# USBHubAndSensors.net
KiCad netlist of a schematic drawn in EAGLE
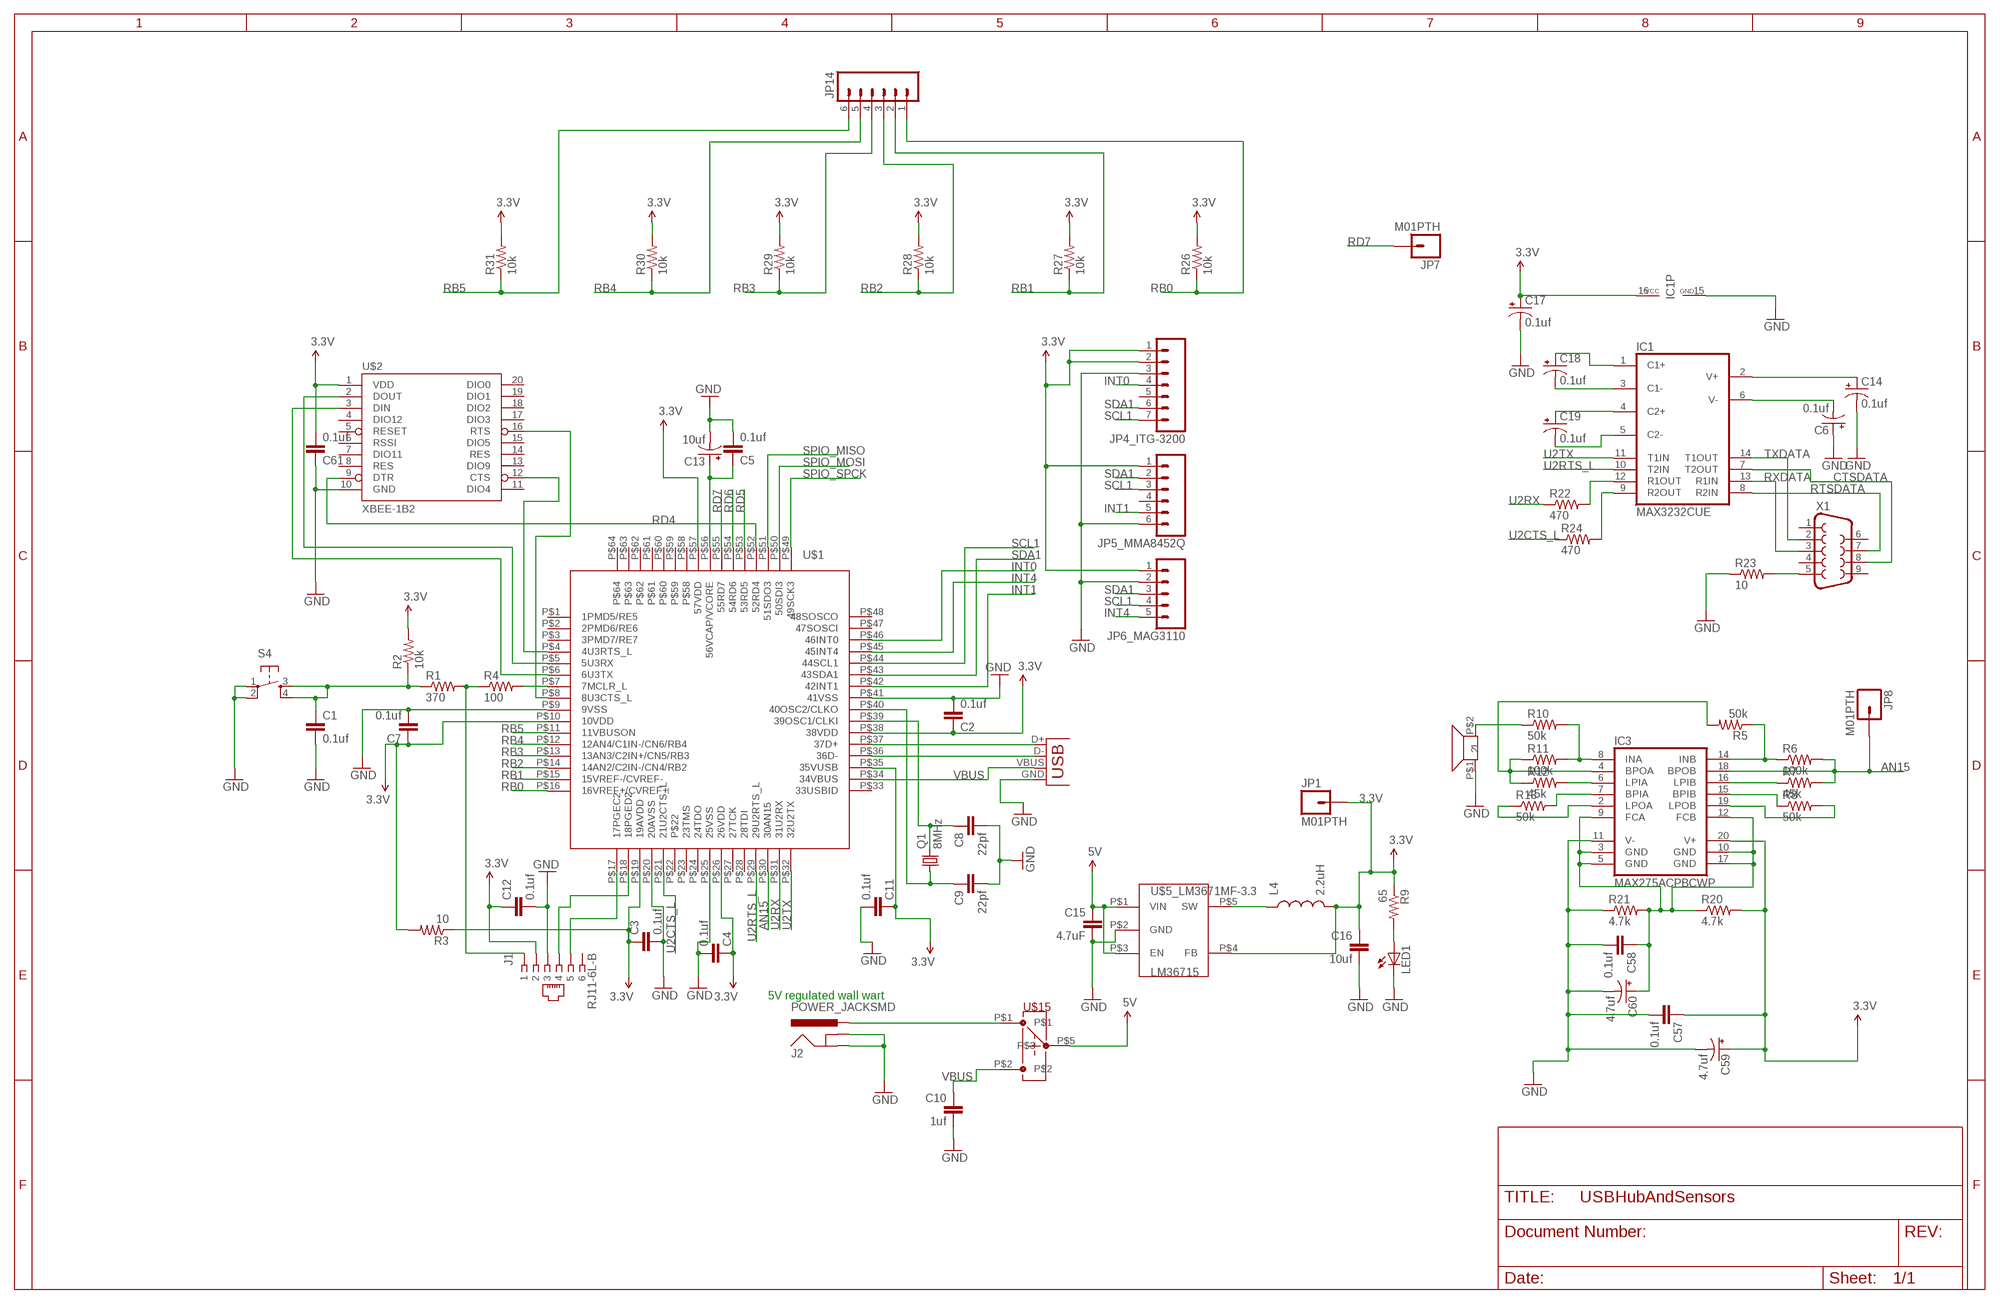
[diagram p0: schematic, sheet 1, part 1 of 2]
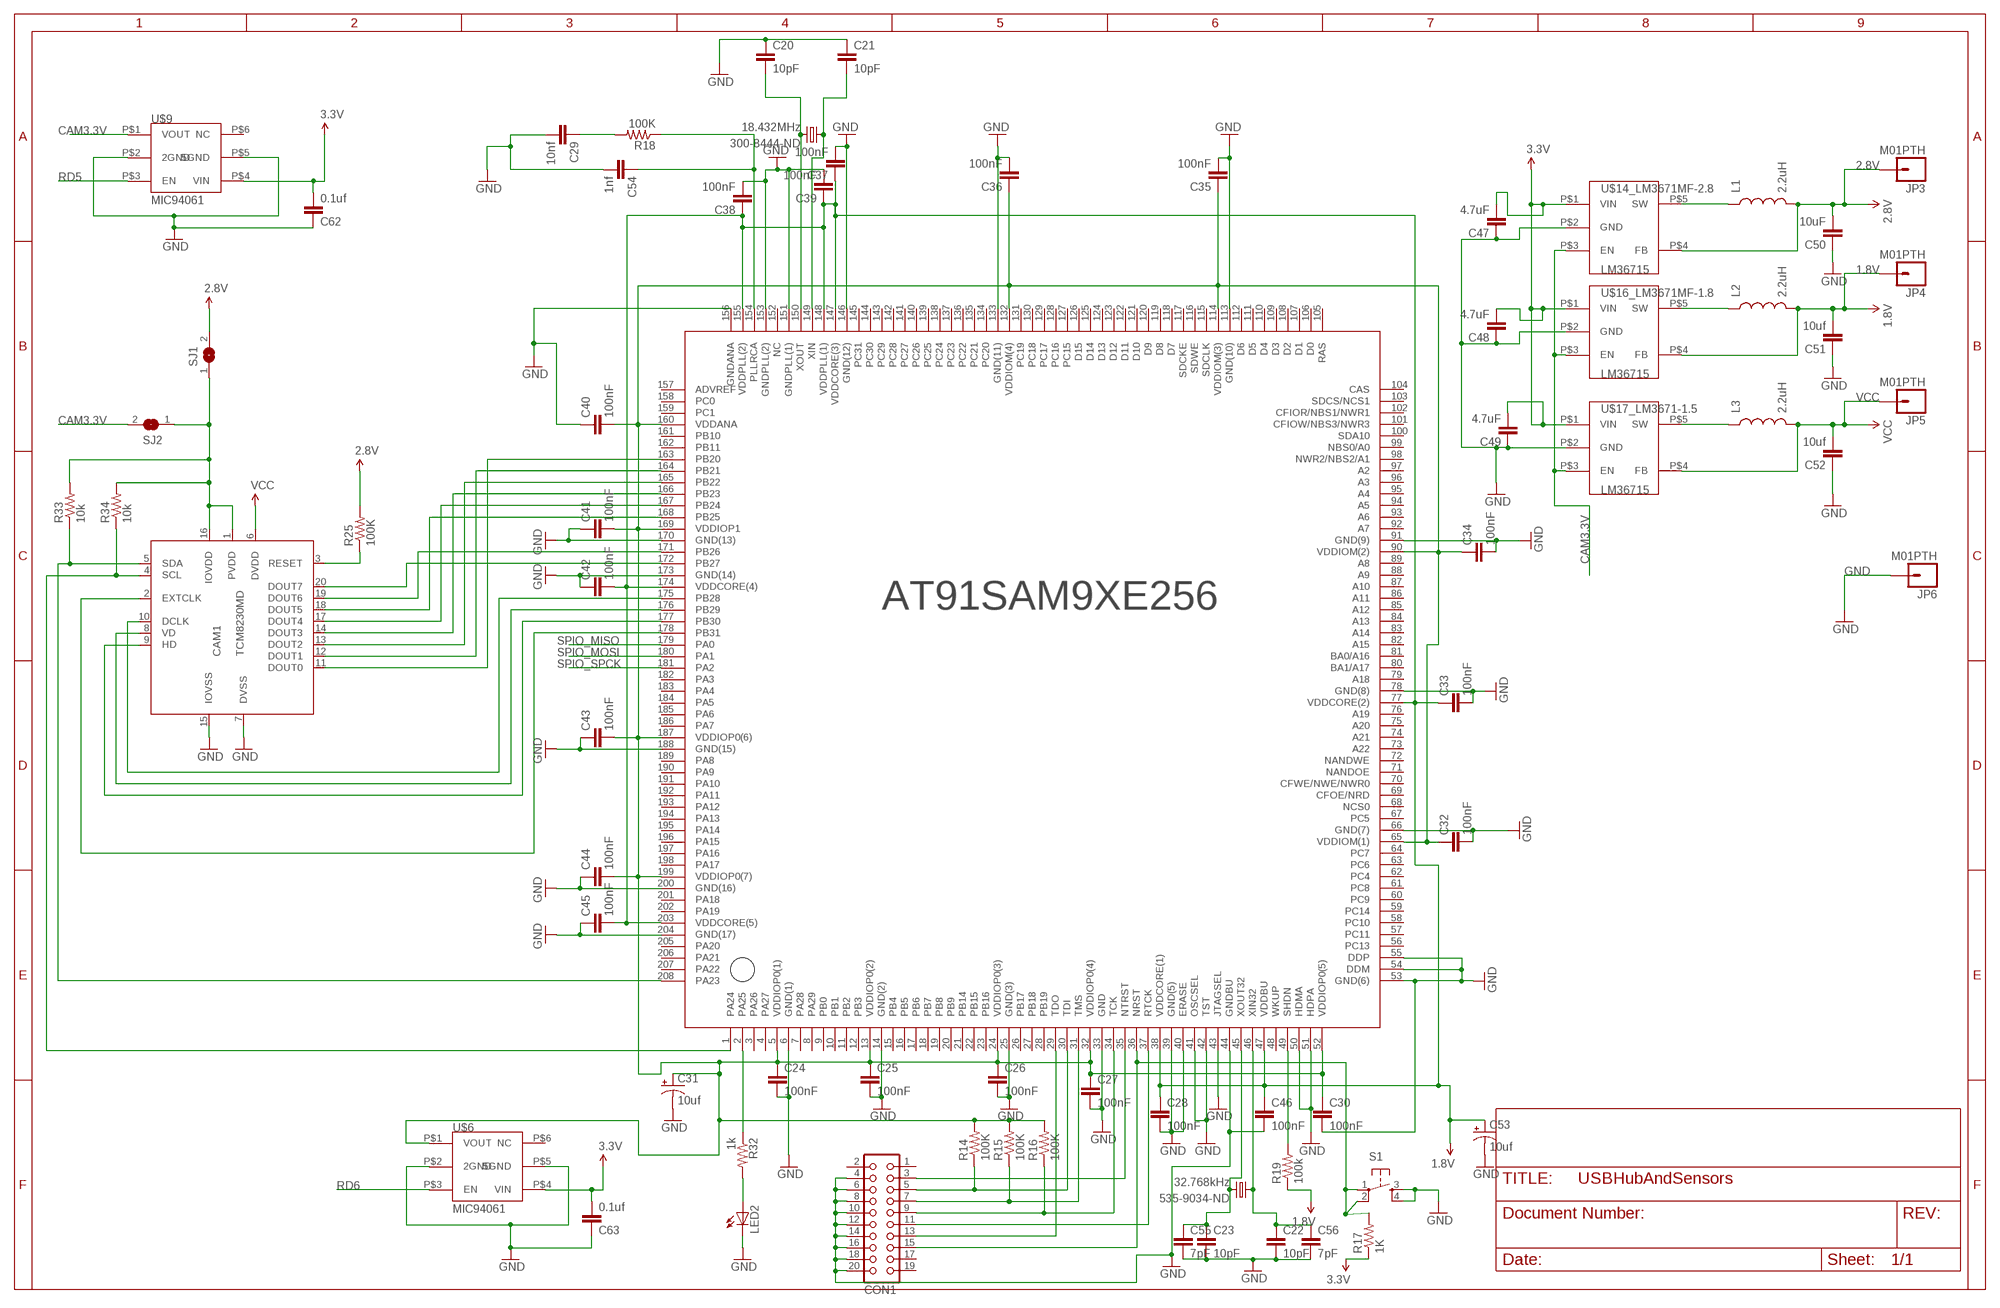
[diagram p1: schematic, sheet 1, part 2 of 2]

(export (version "E")
  (design (tool "Eeschema 10.0.6"))
  (components
    (comp (ref "300-8444-ND")
      (value "18.432MHz")
      (footprint "eagle-import:TC38H")
      (libsource (lib "eagle-import") (part "CRYSTALTC38H"))
    )
    (comp (ref "535-9034-ND")
      (value "32.768kHz")
      (footprint "eagle-import:TC38H")
      (libsource (lib "eagle-import") (part "CRYSTALTC38H"))
    )
    (comp (ref "C1")
      (value "0.1uf")
      (footprint "eagle-import:1206")
      (libsource (lib "eagle-import") (part "CAP1206"))
    )
    (comp (ref "C2")
      (value "0.1uf")
      (footprint "eagle-import:1206")
      (libsource (lib "eagle-import") (part "CAP1206"))
    )
    (comp (ref "C3")
      (value "0.1uf")
      (footprint "eagle-import:1206")
      (libsource (lib "eagle-import") (part "CAP1206"))
    )
    (comp (ref "C4")
      (value "0.1uf")
      (footprint "eagle-import:1206")
      (libsource (lib "eagle-import") (part "CAP1206"))
    )
    (comp (ref "C5")
      (value "0.1uf")
      (footprint "eagle-import:1206")
      (libsource (lib "eagle-import") (part "CAP1206"))
    )
    (comp (ref "C6")
      (value "0.1uf")
      (footprint "eagle-import:EIA3216")
      (libsource (lib "eagle-import") (part "CAP_POL1206"))
    )
    (comp (ref "C7")
      (value "0.1uf")
      (footprint "eagle-import:1206")
      (libsource (lib "eagle-import") (part "CAP1206"))
    )
    (comp (ref "C8")
      (value "22pf")
      (footprint "eagle-import:1206")
      (libsource (lib "eagle-import") (part "CAP1206"))
    )
    (comp (ref "C9")
      (value "22pf")
      (footprint "eagle-import:1206")
      (libsource (lib "eagle-import") (part "CAP1206"))
    )
    (comp (ref "C10")
      (value "1uf")
      (footprint "eagle-import:1206")
      (libsource (lib "eagle-import") (part "CAP1206"))
    )
    (comp (ref "C11")
      (value "0.1uf")
      (footprint "eagle-import:1206")
      (libsource (lib "eagle-import") (part "CAP1206"))
    )
    (comp (ref "C12")
      (value "0.1uf")
      (footprint "eagle-import:1206")
      (libsource (lib "eagle-import") (part "CAP1206"))
    )
    (comp (ref "C13")
      (value "10uf")
      (footprint "eagle-import:EIA3216")
      (libsource (lib "eagle-import") (part "CAP_POL1206"))
    )
    (comp (ref "C14")
      (value "0.1uf")
      (footprint "eagle-import:EIA3216")
      (libsource (lib "eagle-import") (part "CAP_POL1206"))
    )
    (comp (ref "C15")
      (value "4.7uF")
      (footprint "eagle-import:1206")
      (libsource (lib "eagle-import") (part "CAP1206"))
    )
    (comp (ref "C16")
      (value "10uf")
      (footprint "eagle-import:1206")
      (libsource (lib "eagle-import") (part "CAP1206"))
    )
    (comp (ref "C17")
      (value "0.1uf")
      (footprint "eagle-import:EIA3216")
      (libsource (lib "eagle-import") (part "CAP_POL1206"))
    )
    (comp (ref "C18")
      (value "0.1uf")
      (footprint "eagle-import:EIA3216")
      (libsource (lib "eagle-import") (part "CAP_POL1206"))
    )
    (comp (ref "C19")
      (value "0.1uf")
      (footprint "eagle-import:EIA3216")
      (libsource (lib "eagle-import") (part "CAP_POL1206"))
    )
    (comp (ref "C20")
      (value "10pF")
      (footprint "eagle-import:1206")
      (libsource (lib "eagle-import") (part "CAP1206"))
    )
    (comp (ref "C21")
      (value "10pF")
      (footprint "eagle-import:1206")
      (libsource (lib "eagle-import") (part "CAP1206"))
    )
    (comp (ref "C22")
      (value "10pF")
      (footprint "eagle-import:1206")
      (libsource (lib "eagle-import") (part "CAP1206"))
    )
    (comp (ref "C23")
      (value "10pF")
      (footprint "eagle-import:1206")
      (libsource (lib "eagle-import") (part "CAP1206"))
    )
    (comp (ref "C24")
      (value "100nF")
      (footprint "eagle-import:1206")
      (libsource (lib "eagle-import") (part "CAP1206"))
    )
    (comp (ref "C25")
      (value "100nF")
      (footprint "eagle-import:1206")
      (libsource (lib "eagle-import") (part "CAP1206"))
    )
    (comp (ref "C26")
      (value "100nF")
      (footprint "eagle-import:1206")
      (libsource (lib "eagle-import") (part "CAP1206"))
    )
    (comp (ref "C27")
      (value "100nF")
      (footprint "eagle-import:1206")
      (libsource (lib "eagle-import") (part "CAP1206"))
    )
    (comp (ref "C28")
      (value "100nF")
      (footprint "eagle-import:1206")
      (libsource (lib "eagle-import") (part "CAP1206"))
    )
    (comp (ref "C29")
      (value "10nf")
      (footprint "eagle-import:1206")
      (libsource (lib "eagle-import") (part "CAP1206"))
    )
    (comp (ref "C30")
      (value "100nF")
      (footprint "eagle-import:1206")
      (libsource (lib "eagle-import") (part "CAP1206"))
    )
    (comp (ref "C31")
      (value "10uf")
      (footprint "eagle-import:EIA3216")
      (libsource (lib "eagle-import") (part "CAP_POL1206"))
    )
    (comp (ref "C32")
      (value "100nF")
      (footprint "eagle-import:1206")
      (libsource (lib "eagle-import") (part "CAP1206"))
    )
    (comp (ref "C33")
      (value "100nF")
      (footprint "eagle-import:1206")
      (libsource (lib "eagle-import") (part "CAP1206"))
    )
    (comp (ref "C34")
      (value "100nF")
      (footprint "eagle-import:1206")
      (libsource (lib "eagle-import") (part "CAP1206"))
    )
    (comp (ref "C35")
      (value "100nF")
      (footprint "eagle-import:1206")
      (libsource (lib "eagle-import") (part "CAP1206"))
    )
    (comp (ref "C36")
      (value "100nF")
      (footprint "eagle-import:1206")
      (libsource (lib "eagle-import") (part "CAP1206"))
    )
    (comp (ref "C37")
      (value "100nF")
      (footprint "eagle-import:1206")
      (libsource (lib "eagle-import") (part "CAP1206"))
    )
    (comp (ref "C38")
      (value "100nF")
      (footprint "eagle-import:1206")
      (libsource (lib "eagle-import") (part "CAP1206"))
    )
    (comp (ref "C39")
      (value "100nF")
      (footprint "eagle-import:1206")
      (libsource (lib "eagle-import") (part "CAP1206"))
    )
    (comp (ref "C40")
      (value "100nF")
      (footprint "eagle-import:1206")
      (libsource (lib "eagle-import") (part "CAP1206"))
    )
    (comp (ref "C41")
      (value "100nF")
      (footprint "eagle-import:1206")
      (libsource (lib "eagle-import") (part "CAP1206"))
    )
    (comp (ref "C42")
      (value "100nF")
      (footprint "eagle-import:1206")
      (libsource (lib "eagle-import") (part "CAP1206"))
    )
    (comp (ref "C43")
      (value "100nF")
      (footprint "eagle-import:1206")
      (libsource (lib "eagle-import") (part "CAP1206"))
    )
    (comp (ref "C44")
      (value "100nF")
      (footprint "eagle-import:1206")
      (libsource (lib "eagle-import") (part "CAP1206"))
    )
    (comp (ref "C45")
      (value "100nF")
      (footprint "eagle-import:1206")
      (libsource (lib "eagle-import") (part "CAP1206"))
    )
    (comp (ref "C46")
      (value "100nF")
      (footprint "eagle-import:1206")
      (libsource (lib "eagle-import") (part "CAP1206"))
    )
    (comp (ref "C47")
      (value "4.7uF")
      (footprint "eagle-import:1206")
      (libsource (lib "eagle-import") (part "CAP1206"))
    )
    (comp (ref "C48")
      (value "4.7uF")
      (footprint "eagle-import:1206")
      (libsource (lib "eagle-import") (part "CAP1206"))
    )
    (comp (ref "C49")
      (value "4.7uF")
      (footprint "eagle-import:1206")
      (libsource (lib "eagle-import") (part "CAP1206"))
    )
    (comp (ref "C50")
      (value "10uF")
      (footprint "eagle-import:1206")
      (libsource (lib "eagle-import") (part "CAP1206"))
    )
    (comp (ref "C51")
      (value "10uf")
      (footprint "eagle-import:1206")
      (libsource (lib "eagle-import") (part "CAP1206"))
    )
    (comp (ref "C52")
      (value "10uf")
      (footprint "eagle-import:1206")
      (libsource (lib "eagle-import") (part "CAP1206"))
    )
    (comp (ref "C53")
      (value "10uf")
      (footprint "eagle-import:EIA3216")
      (libsource (lib "eagle-import") (part "CAP_POL1206"))
    )
    (comp (ref "C54")
      (value "1nf")
      (footprint "eagle-import:1206")
      (libsource (lib "eagle-import") (part "CAP1206"))
    )
    (comp (ref "C55")
      (value "7pF")
      (footprint "eagle-import:1206")
      (libsource (lib "eagle-import") (part "CAP1206"))
    )
    (comp (ref "C56")
      (value "7pF")
      (footprint "eagle-import:1206")
      (libsource (lib "eagle-import") (part "CAP1206"))
    )
    (comp (ref "C57")
      (value "0.1uf")
      (footprint "eagle-import:1206")
      (libsource (lib "eagle-import") (part "CAP1206"))
    )
    (comp (ref "C58")
      (value "0.1uf")
      (footprint "eagle-import:1206")
      (libsource (lib "eagle-import") (part "CAP1206"))
    )
    (comp (ref "C59")
      (value "4.7uf")
      (footprint "eagle-import:EIA3216")
      (libsource (lib "eagle-import") (part "CAP_POL1206"))
    )
    (comp (ref "C60")
      (value "4.7uf")
      (footprint "eagle-import:EIA3216")
      (libsource (lib "eagle-import") (part "CAP_POL1206"))
    )
    (comp (ref "C61")
      (value "0.1uf")
      (footprint "eagle-import:1206")
      (libsource (lib "eagle-import") (part "CAP1206"))
    )
    (comp (ref "C62")
      (value "0.1uf")
      (footprint "eagle-import:1206")
      (libsource (lib "eagle-import") (part "CAP1206"))
    )
    (comp (ref "C63")
      (value "0.1uf")
      (footprint "eagle-import:1206")
      (libsource (lib "eagle-import") (part "CAP1206"))
    )
    (comp (ref "CAM1")
      (value "TCM8230MD")
      (footprint "eagle-import:TCM8230MD")
      (libsource (lib "eagle-import") (part "TCM8230MD"))
    )
    (comp (ref "CON1")
      (value "CON20")
      (footprint "eagle-import:CON20")
      (libsource (lib "eagle-import") (part "CON20"))
    )
    (comp (ref "IC1")
      (value "MAX3232CUE")
      (footprint "eagle-import:TSSOP16")
      (fields (field (name "MF") "MAXIM") (field (name "MPN") "MAX3232CUE+"))
      (libsource (lib "eagle-import") (part "MAX3232UEC"))
    )
    (comp (ref "IC3")
      (value "MAX275ACPBCWP")
      (footprint "eagle-import:SO20L")
      (libsource (lib "eagle-import") (part "MAX275ACPBCWP"))
    )
    (comp (ref "J1")
      (value "RJ11-6L-B")
      (footprint "eagle-import:RJ11-NO_SHIELD")
      (fields (field (name "MF") "TYCO ELECTRONICS"))
      (libsource (lib "eagle-import") (part "RJ11-6L-B"))
    )
    (comp (ref "J2")
      (value "POWER_JACKSMD")
      (footprint "eagle-import:POWER_JACK_SMD")
      (libsource (lib "eagle-import") (part "POWER_JACKSMD"))
    )
    (comp (ref "JP1")
      (value "M01PTH")
      (footprint "eagle-import:1X01")
      (libsource (lib "eagle-import") (part "M01PTH"))
    )
    (comp (ref "JP3")
      (value "M01PTH")
      (footprint "eagle-import:1X01")
      (libsource (lib "eagle-import") (part "M01PTH"))
    )
    (comp (ref "JP4")
      (value "M01PTH")
      (footprint "eagle-import:1X01")
      (libsource (lib "eagle-import") (part "M01PTH"))
    )
    (comp (ref "JP4_ITG-3200")
      (value "M07")
      (footprint "eagle-import:1X07")
      (libsource (lib "eagle-import") (part "M07"))
    )
    (comp (ref "JP5")
      (value "M01PTH")
      (footprint "eagle-import:1X01")
      (libsource (lib "eagle-import") (part "M01PTH"))
    )
    (comp (ref "JP5_MMA8452Q")
      (value "M06SIP")
      (footprint "eagle-import:1X06")
      (libsource (lib "eagle-import") (part "M06SIP"))
    )
    (comp (ref "JP6")
      (value "M01PTH")
      (footprint "eagle-import:1X01")
      (libsource (lib "eagle-import") (part "M01PTH"))
    )
    (comp (ref "JP6_MAG3110")
      (value "M05PTH")
      (footprint "eagle-import:1X05")
      (libsource (lib "eagle-import") (part "M05PTH"))
    )
    (comp (ref "JP7")
      (value "M01PTH")
      (footprint "eagle-import:1X01")
      (libsource (lib "eagle-import") (part "M01PTH"))
    )
    (comp (ref "JP8")
      (value "M01PTH")
      (footprint "eagle-import:1X01")
      (libsource (lib "eagle-import") (part "M01PTH"))
    )
    (comp (ref "JP14")
      (value "M06SIP")
      (footprint "eagle-import:1X06")
      (libsource (lib "eagle-import") (part "M06SIP"))
    )
    (comp (ref "L1")
      (value "2.2uH")
      (footprint "eagle-import:1210")
      (libsource (lib "eagle-import") (part "INDUCTOR1210"))
    )
    (comp (ref "L2")
      (value "2.2uH")
      (footprint "eagle-import:1210")
      (libsource (lib "eagle-import") (part "INDUCTOR1210"))
    )
    (comp (ref "L3")
      (value "2.2uH")
      (footprint "eagle-import:1210")
      (libsource (lib "eagle-import") (part "INDUCTOR1210"))
    )
    (comp (ref "L4")
      (value "2.2uH")
      (footprint "eagle-import:1210")
      (libsource (lib "eagle-import") (part "INDUCTOR1210"))
    )
    (comp (ref "LED1")
      (value "LED-FKIT-1206")
      (footprint "eagle-import:FKIT-LED-1206")
      (libsource (lib "eagle-import") (part "LED-FKIT-1206"))
    )
    (comp (ref "LED2")
      (value "LED-FKIT-1206")
      (footprint "eagle-import:FKIT-LED-1206")
      (libsource (lib "eagle-import") (part "LED-FKIT-1206"))
    )
    (comp (ref "Q1")
      (value "8MHz")
      (footprint "eagle-import:HC49UP")
      (libsource (lib "eagle-import") (part "CRYSTALHC49UP"))
    )
    (comp (ref "R1")
      (value "370")
      (footprint "eagle-import:1206")
      (libsource (lib "eagle-import") (part "RESISTOR1206"))
    )
    (comp (ref "R2")
      (value "10k")
      (footprint "eagle-import:1206")
      (libsource (lib "eagle-import") (part "RESISTOR1206"))
    )
    (comp (ref "R3")
      (value "10")
      (footprint "eagle-import:1206")
      (libsource (lib "eagle-import") (part "RESISTOR1206"))
    )
    (comp (ref "R4")
      (value "100")
      (footprint "eagle-import:1206")
      (libsource (lib "eagle-import") (part "RESISTOR1206"))
    )
    (comp (ref "R5")
      (value "50k")
      (footprint "eagle-import:1206")
      (libsource (lib "eagle-import") (part "RESISTOR1206"))
    )
    (comp (ref "R6")
      (value "100k")
      (footprint "eagle-import:1206")
      (libsource (lib "eagle-import") (part "RESISTOR1206"))
    )
    (comp (ref "R7")
      (value "45k")
      (footprint "eagle-import:1206")
      (libsource (lib "eagle-import") (part "RESISTOR1206"))
    )
    (comp (ref "R8")
      (value "50k")
      (footprint "eagle-import:1206")
      (libsource (lib "eagle-import") (part "RESISTOR1206"))
    )
    (comp (ref "R9")
      (value "65")
      (footprint "eagle-import:1206")
      (libsource (lib "eagle-import") (part "RESISTOR1206"))
    )
    (comp (ref "R10")
      (value "50k")
      (footprint "eagle-import:1206")
      (libsource (lib "eagle-import") (part "RESISTOR1206"))
    )
    (comp (ref "R11")
      (value "100k")
      (footprint "eagle-import:1206")
      (libsource (lib "eagle-import") (part "RESISTOR1206"))
    )
    (comp (ref "R12")
      (value "45k")
      (footprint "eagle-import:1206")
      (libsource (lib "eagle-import") (part "RESISTOR1206"))
    )
    (comp (ref "R13")
      (value "50k")
      (footprint "eagle-import:1206")
      (libsource (lib "eagle-import") (part "RESISTOR1206"))
    )
    (comp (ref "R14")
      (value "100K")
      (footprint "eagle-import:1206")
      (libsource (lib "eagle-import") (part "RESISTOR1206"))
    )
    (comp (ref "R15")
      (value "100K")
      (footprint "eagle-import:1206")
      (libsource (lib "eagle-import") (part "RESISTOR1206"))
    )
    (comp (ref "R16")
      (value "100K")
      (footprint "eagle-import:1206")
      (libsource (lib "eagle-import") (part "RESISTOR1206"))
    )
    (comp (ref "R17")
      (value "1K")
      (footprint "eagle-import:1206")
      (libsource (lib "eagle-import") (part "RESISTOR1206"))
    )
    (comp (ref "R18")
      (value "100K")
      (footprint "eagle-import:1206")
      (libsource (lib "eagle-import") (part "RESISTOR1206"))
    )
    (comp (ref "R19")
      (value "100k")
      (footprint "eagle-import:1206")
      (libsource (lib "eagle-import") (part "RESISTOR1206"))
    )
    (comp (ref "R20")
      (value "4.7k")
      (footprint "eagle-import:1206")
      (libsource (lib "eagle-import") (part "RESISTOR1206"))
    )
    (comp (ref "R21")
      (value "4.7k")
      (footprint "eagle-import:1206")
      (libsource (lib "eagle-import") (part "RESISTOR1206"))
    )
    (comp (ref "R22")
      (value "470")
      (footprint "eagle-import:1206")
      (libsource (lib "eagle-import") (part "RESISTOR1206"))
    )
    (comp (ref "R23")
      (value "10")
      (footprint "eagle-import:1206")
      (libsource (lib "eagle-import") (part "RESISTOR1206"))
    )
    (comp (ref "R24")
      (value "470")
      (footprint "eagle-import:1206")
      (libsource (lib "eagle-import") (part "RESISTOR1206"))
    )
    (comp (ref "R25")
      (value "100K")
      (footprint "eagle-import:1206")
      (libsource (lib "eagle-import") (part "RESISTOR1206"))
    )
    (comp (ref "R26")
      (value "10k")
      (footprint "eagle-import:1206")
      (libsource (lib "eagle-import") (part "RESISTOR1206"))
    )
    (comp (ref "R27")
      (value "10k")
      (footprint "eagle-import:1206")
      (libsource (lib "eagle-import") (part "RESISTOR1206"))
    )
    (comp (ref "R28")
      (value "10k")
      (footprint "eagle-import:1206")
      (libsource (lib "eagle-import") (part "RESISTOR1206"))
    )
    (comp (ref "R29")
      (value "10k")
      (footprint "eagle-import:1206")
      (libsource (lib "eagle-import") (part "RESISTOR1206"))
    )
    (comp (ref "R30")
      (value "10k")
      (footprint "eagle-import:1206")
      (libsource (lib "eagle-import") (part "RESISTOR1206"))
    )
    (comp (ref "R31")
      (value "10k")
      (footprint "eagle-import:1206")
      (libsource (lib "eagle-import") (part "RESISTOR1206"))
    )
    (comp (ref "R32")
      (value "1k")
      (footprint "eagle-import:1206")
      (libsource (lib "eagle-import") (part "RESISTOR1206"))
    )
    (comp (ref "R33")
      (value "10k")
      (footprint "eagle-import:1206")
      (libsource (lib "eagle-import") (part "RESISTOR1206"))
    )
    (comp (ref "R34")
      (value "10k")
      (footprint "eagle-import:1206")
      (libsource (lib "eagle-import") (part "RESISTOR1206"))
    )
    (comp (ref "S1")
      (value "TAC_SWITCHPTH")
      (footprint "eagle-import:TACTILE-PTH")
      (libsource (lib "eagle-import") (part "TAC_SWITCHPTH"))
    )
    (comp (ref "S4")
      (value "TAC_SWITCHPTH")
      (footprint "eagle-import:TACTILE-PTH")
      (libsource (lib "eagle-import") (part "TAC_SWITCHPTH"))
    )
    (comp (ref "SJ1") (value "SJ") (footprint "eagle-import:SJ") (libsource (lib "eagle-import") (part "SJ")))
    (comp (ref "SJ2") (value "SJ") (footprint "eagle-import:SJ") (libsource (lib "eagle-import") (part "SJ")))
    (comp (ref "U$1")
      (value "PIC32MX534F06HTQFP")
      (footprint "eagle-import:64-TQFP")
      (libsource (lib "eagle-import") (part "PIC32MX534F06HTQFP"))
    )
    (comp (ref "U$2")
      (value "XBEE-1B2")
      (footprint "eagle-import:XBEE-SILK")
      (libsource (lib "eagle-import") (part "XBEE-1B2"))
    )
    (comp (ref "U$5")
      (value "40TR-12B")
      (footprint "eagle-import:40TR")
      (libsource (lib "eagle-import") (part "40TR-12B"))
    )
    (comp (ref "U$5_LM3671MF-3.3")
      (value "LM36715")
      (footprint "eagle-import:SOT23-5")
      (libsource (lib "eagle-import") (part "LM36715"))
    )
    (comp (ref "U$6")
      (value "MIC94061YC6")
      (footprint "eagle-import:SC-70-6")
      (libsource (lib "eagle-import") (part "MIC94061YC6"))
    )
    (comp (ref "U$7")
      (value "AT91SAM9XE256")
      (footprint "eagle-import:PQFP208")
      (libsource (lib "eagle-import") (part "AT91SAM9XE256"))
    )
    (comp (ref "U$9")
      (value "MIC94061YC6")
      (footprint "eagle-import:SC-70-6")
      (libsource (lib "eagle-import") (part "MIC94061YC6"))
    )
    (comp (ref "U$14_LM3671MF-2.8")
      (value "LM36715")
      (footprint "eagle-import:SOT23-5")
      (libsource (lib "eagle-import") (part "LM36715"))
    )
    (comp (ref "U$15")
      (value "G-107PLUG-IN")
      (footprint "eagle-import:G-197")
      (libsource (lib "eagle-import") (part "G-107PLUG-IN"))
    )
    (comp (ref "U$16_LM3671MF-1.8")
      (value "LM36715")
      (footprint "eagle-import:SOT23-5")
      (libsource (lib "eagle-import") (part "LM36715"))
    )
    (comp (ref "U$17_LM3671-1.5")
      (value "LM36715")
      (footprint "eagle-import:SOT23-5")
      (libsource (lib "eagle-import") (part "LM36715"))
    )
    (comp (ref "X1")
      (value "DB9FEMALE")
      (footprint "eagle-import:DB9")
      (libsource (lib "eagle-import") (part "DB9FEMALE"))
    )
    (comp (ref "X2")
      (value "USB-MICROB")
      (footprint "eagle-import:USB-MICROB")
      (libsource (lib "eagle-import") (part "USB-MICROB"))
    )
  )
  (nets
    (net (code "1") (name "/AN15") (class "Default")
      (node (ref "IC3") (pin "18") (pinfunction "BPOB_18") (pintype "output"))
      (node (ref "JP8") (pin "1") (pinfunction "1_1") (pintype "passive"))
      (node (ref "R6") (pin "2") (pinfunction "2_2") (pintype "passive"))
      (node (ref "R7") (pin "2") (pinfunction "2_2") (pintype "passive"))
      (node (ref "U$1") (pin "P$30") (pinfunction "30AN15_P$30") (pintype "bidirectional"))
    )
    (net (code "2") (name "/CAM3.3V") (class "Default")
      (node (ref "SJ2") (pin "2") (pinfunction "2_2") (pintype "passive"))
      (node (ref "U$14_LM3671MF-2.8") (pin "P$3") (pinfunction "EN_P$3") (pintype "bidirectional"))
      (node (ref "U$16_LM3671MF-1.8") (pin "P$3") (pinfunction "EN_P$3") (pintype "bidirectional"))
      (node (ref "U$17_LM3671-1.5") (pin "P$3") (pinfunction "EN_P$3") (pintype "bidirectional"))
      (node (ref "U$9") (pin "P$1") (pinfunction "VOUT_P$1") (pintype "bidirectional"))
    )
    (net (code "3") (name "/CTSDATA") (class "Default")
      (node (ref "IC1") (pin "7") (pinfunction "T2OUT_7") (pintype "output"))
      (node (ref "X1") (pin "8") (pinfunction "8_8") (pintype "passive"))
    )
    (net (code "4") (name "/INT0") (class "Default")
      (node (ref "JP4_ITG-3200") (pin "4") (pinfunction "4_4") (pintype "passive"))
      (node (ref "U$1") (pin "P$46") (pinfunction "46INT0_P$46") (pintype "bidirectional"))
    )
    (net (code "5") (name "/INT1") (class "Default")
      (node (ref "JP5_MMA8452Q") (pin "5") (pinfunction "5_5") (pintype "passive"))
      (node (ref "U$1") (pin "P$42") (pinfunction "42INT1_P$42") (pintype "bidirectional"))
    )
    (net (code "6") (name "/INT4") (class "Default")
      (node (ref "JP6_MAG3110") (pin "5") (pinfunction "5_5") (pintype "passive"))
      (node (ref "U$1") (pin "P$45") (pinfunction "45INT4_P$45") (pintype "bidirectional"))
    )
    (net (code "7") (name "/RB0") (class "Default")
      (node (ref "JP14") (pin "1") (pinfunction "1_1") (pintype "passive"))
      (node (ref "R26") (pin "1") (pinfunction "1_1") (pintype "passive"))
      (node (ref "U$1") (pin "P$16") (pinfunction "16VREF+/CVREF+_P$16") (pintype "bidirectional"))
    )
    (net (code "8") (name "/RB1") (class "Default")
      (node (ref "JP14") (pin "2") (pinfunction "2_2") (pintype "passive"))
      (node (ref "R27") (pin "1") (pinfunction "1_1") (pintype "passive"))
      (node (ref "U$1") (pin "P$15") (pinfunction "15VREF-/CVREF-_P$15") (pintype "bidirectional"))
    )
    (net (code "9") (name "/RB2") (class "Default")
      (node (ref "JP14") (pin "3") (pinfunction "3_3") (pintype "passive"))
      (node (ref "R28") (pin "1") (pinfunction "1_1") (pintype "passive"))
      (node (ref "U$1") (pin "P$14") (pinfunction "14AN2/C2IN-/CN4/RB2_P$14") (pintype "bidirectional"))
    )
    (net (code "10") (name "/RB3") (class "Default")
      (node (ref "JP14") (pin "4") (pinfunction "4_4") (pintype "passive"))
      (node (ref "R29") (pin "1") (pinfunction "1_1") (pintype "passive"))
      (node (ref "U$1") (pin "P$13") (pinfunction "13AN3/C2IN+/CN5/RB3_P$13") (pintype "bidirectional"))
    )
    (net (code "11") (name "/RB4") (class "Default")
      (node (ref "JP14") (pin "5") (pinfunction "5_5") (pintype "passive"))
      (node (ref "R30") (pin "1") (pinfunction "1_1") (pintype "passive"))
      (node (ref "U$1") (pin "P$12") (pinfunction "12AN4/C1IN-/CN6/RB4_P$12") (pintype "bidirectional"))
    )
    (net (code "12") (name "/RB5") (class "Default")
      (node (ref "JP14") (pin "6") (pinfunction "6_6") (pintype "passive"))
      (node (ref "R31") (pin "1") (pinfunction "1_1") (pintype "passive"))
      (node (ref "U$1") (pin "P$11") (pinfunction "11VBUSON_P$11") (pintype "bidirectional"))
    )
    (net (code "13") (name "/RD4") (class "Default")
      (node (ref "U$1") (pin "P$52") (pinfunction "52RD4_P$52") (pintype "bidirectional"))
      (node (ref "U$2") (pin "9") (pinfunction "DTR_9") (pintype "bidirectional"))
    )
    (net (code "14") (name "/RD5") (class "Default")
      (node (ref "U$1") (pin "P$53") (pinfunction "53RD5_P$53") (pintype "bidirectional"))
      (node (ref "U$9") (pin "P$3") (pinfunction "EN_P$3") (pintype "bidirectional"))
    )
    (net (code "15") (name "/RD6") (class "Default")
      (node (ref "U$1") (pin "P$54") (pinfunction "54RD6_P$54") (pintype "bidirectional"))
      (node (ref "U$6") (pin "P$3") (pinfunction "EN_P$3") (pintype "bidirectional"))
    )
    (net (code "16") (name "/RD7") (class "Default")
      (node (ref "JP7") (pin "1") (pinfunction "1_1") (pintype "passive"))
      (node (ref "U$1") (pin "P$55") (pinfunction "55RD7_P$55") (pintype "bidirectional"))
    )
    (net (code "17") (name "/RTSDATA") (class "Default")
      (node (ref "IC1") (pin "8") (pinfunction "R2IN_8") (pintype "input"))
      (node (ref "X1") (pin "7") (pinfunction "7_7") (pintype "passive"))
    )
    (net (code "18") (name "/RXDATA") (class "Default")
      (node (ref "IC1") (pin "13") (pinfunction "R1IN_13") (pintype "input"))
      (node (ref "X1") (pin "3") (pinfunction "3_3") (pintype "passive"))
    )
    (net (code "19") (name "/SCL1") (class "Default")
      (node (ref "JP4_ITG-3200") (pin "7") (pinfunction "7_7") (pintype "passive"))
      (node (ref "JP5_MMA8452Q") (pin "3") (pinfunction "3_3") (pintype "passive"))
      (node (ref "JP6_MAG3110") (pin "4") (pinfunction "4_4") (pintype "passive"))
      (node (ref "U$1") (pin "P$44") (pinfunction "44SCL1_P$44") (pintype "bidirectional"))
    )
    (net (code "20") (name "/SDA1") (class "Default")
      (node (ref "JP4_ITG-3200") (pin "6") (pinfunction "6_6") (pintype "passive"))
      (node (ref "JP5_MMA8452Q") (pin "2") (pinfunction "2_2") (pintype "passive"))
      (node (ref "JP6_MAG3110") (pin "3") (pinfunction "3_3") (pintype "passive"))
      (node (ref "U$1") (pin "P$43") (pinfunction "43SDA1_P$43") (pintype "bidirectional"))
    )
    (net (code "21") (name "/SPIO_MISO") (class "Default")
      (node (ref "U$1") (pin "P$51") (pinfunction "51SDO3_P$51") (pintype "bidirectional"))
      (node (ref "U$7") (pin "179") (pinfunction "PA0_179") (pintype "bidirectional"))
    )
    (net (code "22") (name "/SPIO_MOSI") (class "Default")
      (node (ref "U$1") (pin "P$50") (pinfunction "50SDI3_P$50") (pintype "bidirectional"))
      (node (ref "U$7") (pin "180") (pinfunction "PA1_180") (pintype "bidirectional"))
    )
    (net (code "23") (name "/SPIO_SPCK") (class "Default")
      (node (ref "U$1") (pin "P$49") (pinfunction "49SCK3_P$49") (pintype "bidirectional"))
      (node (ref "U$7") (pin "181") (pinfunction "PA2_181") (pintype "bidirectional"))
    )
    (net (code "24") (name "/TXDATA") (class "Default")
      (node (ref "IC1") (pin "14") (pinfunction "T1OUT_14") (pintype "output"))
      (node (ref "X1") (pin "2") (pinfunction "2_2") (pintype "passive"))
    )
    (net (code "25") (name "/U2CTS_L") (class "Default")
      (node (ref "R24") (pin "1") (pinfunction "1_1") (pintype "passive"))
      (node (ref "U$1") (pin "P$21") (pinfunction "21U2CTS_L_P$21") (pintype "bidirectional"))
    )
    (net (code "26") (name "/U2RTS_L") (class "Default")
      (node (ref "IC1") (pin "10") (pinfunction "T2IN_10") (pintype "input"))
      (node (ref "U$1") (pin "P$29") (pinfunction "29U2RTS_L_P$29") (pintype "bidirectional"))
    )
    (net (code "27") (name "/U2RX") (class "Default")
      (node (ref "R22") (pin "1") (pinfunction "1_1") (pintype "passive"))
      (node (ref "U$1") (pin "P$31") (pinfunction "31U2RX_P$31") (pintype "bidirectional"))
    )
    (net (code "28") (name "/U2TX") (class "Default")
      (node (ref "IC1") (pin "11") (pinfunction "T1IN_11") (pintype "input"))
      (node (ref "U$1") (pin "P$32") (pinfunction "32U2TX_P$32") (pintype "bidirectional"))
    )
    (net (code "29") (name "/VBUS") (class "Default")
      (node (ref "C10") (pin "1") (pinfunction "1_1") (pintype "passive"))
      (node (ref "U$1") (pin "P$34") (pinfunction "34VBUS_P$34") (pintype "bidirectional"))
      (node (ref "U$15") (pin "P$2") (pinfunction "P$2_P$2") (pintype "bidirectional"))
      (node (ref "X2") (pin "VBUS") (pinfunction "VBUS_VBUS") (pintype "bidirectional"))
    )
    (net (code "30") (name "1.8V") (class "Default")
      (node (ref "C28") (pin "1") (pinfunction "1_1") (pintype "passive"))
      (node (ref "C33") (pin "1") (pinfunction "1_1") (pintype "passive"))
      (node (ref "C37") (pin "1") (pinfunction "1_1") (pintype "passive"))
      (node (ref "C38") (pin "1") (pinfunction "1_1") (pintype "passive"))
      (node (ref "C39") (pin "1") (pinfunction "1_1") (pintype "passive"))
      (node (ref "C42") (pin "2") (pinfunction "2_2") (pintype "passive"))
      (node (ref "C45") (pin "2") (pinfunction "2_2") (pintype "passive"))
      (node (ref "C46") (pin "1") (pinfunction "1_1") (pintype "passive"))
      (node (ref "C51") (pin "2") (pinfunction "2_2") (pintype "passive"))
      (node (ref "C53") (pin "A") (pinfunction "+_A") (pintype "passive"))
      (node (ref "JP4") (pin "1") (pinfunction "1_1") (pintype "passive"))
      (node (ref "L2") (pin "2") (pinfunction "2_2") (pintype "passive"))
      (node (ref "R19") (pin "1") (pinfunction "1_1") (pintype "passive"))
      (node (ref "U$16_LM3671MF-1.8") (pin "P$4") (pinfunction "FB_P$4") (pintype "bidirectional"))
      (node (ref "U$7") (pin "147") (pinfunction "VDDCORE(3)_147") (pintype "bidirectional"))
      (node (ref "U$7") (pin "148") (pinfunction "VDDPLL(1)_148") (pintype "bidirectional"))
      (node (ref "U$7") (pin "155") (pinfunction "VDDPLL(2)_155") (pintype "bidirectional"))
      (node (ref "U$7") (pin "174") (pinfunction "VDDCORE(4)_174") (pintype "bidirectional"))
      (node (ref "U$7") (pin "203") (pinfunction "VDDCORE(5)_203") (pintype "bidirectional"))
      (node (ref "U$7") (pin "38") (pinfunction "VDDCORE(1)_38") (pintype "bidirectional"))
      (node (ref "U$7") (pin "47") (pinfunction "VDDBU_47") (pintype "bidirectional"))
      (node (ref "U$7") (pin "77") (pinfunction "VDDCORE(2)_77") (pintype "bidirectional"))
    )
    (net (code "31") (name "2.8V") (class "Default")
      (node (ref "C50") (pin "2") (pinfunction "2_2") (pintype "passive"))
      (node (ref "JP3") (pin "1") (pinfunction "1_1") (pintype "passive"))
      (node (ref "L1") (pin "2") (pinfunction "2_2") (pintype "passive"))
      (node (ref "R25") (pin "2") (pinfunction "2_2") (pintype "passive"))
      (node (ref "SJ1") (pin "2") (pinfunction "2_2") (pintype "passive"))
      (node (ref "U$14_LM3671MF-2.8") (pin "P$4") (pinfunction "FB_P$4") (pintype "bidirectional"))
    )
    (net (code "32") (name "3.3V") (class "Default")
      (node (ref "C11") (pin "1") (pinfunction "1_1") (pintype "passive"))
      (node (ref "C12") (pin "1") (pinfunction "1_1") (pintype "passive"))
      (node (ref "C16") (pin "1") (pinfunction "1_1") (pintype "passive"))
      (node (ref "C17") (pin "A") (pinfunction "+_A") (pintype "passive"))
      (node (ref "C2") (pin "1") (pinfunction "1_1") (pintype "passive"))
      (node (ref "C3") (pin "1") (pinfunction "1_1") (pintype "passive"))
      (node (ref "C4") (pin "1") (pinfunction "1_1") (pintype "passive"))
      (node (ref "C47") (pin "2") (pinfunction "2_2") (pintype "passive"))
      (node (ref "C48") (pin "2") (pinfunction "2_2") (pintype "passive"))
      (node (ref "C49") (pin "2") (pinfunction "2_2") (pintype "passive"))
      (node (ref "C57") (pin "1") (pinfunction "1_1") (pintype "passive"))
      (node (ref "C59") (pin "A") (pinfunction "+_A") (pintype "passive"))
      (node (ref "C61") (pin "2") (pinfunction "2_2") (pintype "passive"))
      (node (ref "C62") (pin "2") (pinfunction "2_2") (pintype "passive"))
      (node (ref "C63") (pin "2") (pinfunction "2_2") (pintype "passive"))
      (node (ref "C7") (pin "1") (pinfunction "1_1") (pintype "passive"))
      (node (ref "IC1") (pin "16") (pinfunction "VCC_16") (pintype "power_in"))
      (node (ref "IC3") (pin "20") (pinfunction "V+_20") (pintype "power_in"))
      (node (ref "J1") (pin "2") (pinfunction "2_2") (pintype "passive"))
      (node (ref "JP1") (pin "1") (pinfunction "1_1") (pintype "passive"))
      (node (ref "JP4_ITG-3200") (pin "1") (pinfunction "1_1") (pintype "passive"))
      (node (ref "JP4_ITG-3200") (pin "2") (pinfunction "2_2") (pintype "passive"))
      (node (ref "JP5_MMA8452Q") (pin "1") (pinfunction "1_1") (pintype "passive"))
      (node (ref "JP6_MAG3110") (pin "1") (pinfunction "1_1") (pintype "passive"))
      (node (ref "L4") (pin "2") (pinfunction "2_2") (pintype "passive"))
      (node (ref "R17") (pin "1") (pinfunction "1_1") (pintype "passive"))
      (node (ref "R2") (pin "2") (pinfunction "2_2") (pintype "passive"))
      (node (ref "R20") (pin "2") (pinfunction "2_2") (pintype "passive"))
      (node (ref "R26") (pin "2") (pinfunction "2_2") (pintype "passive"))
      (node (ref "R27") (pin "2") (pinfunction "2_2") (pintype "passive"))
      (node (ref "R28") (pin "2") (pinfunction "2_2") (pintype "passive"))
      (node (ref "R29") (pin "2") (pinfunction "2_2") (pintype "passive"))
      (node (ref "R3") (pin "1") (pinfunction "1_1") (pintype "passive"))
      (node (ref "R3") (pin "2") (pinfunction "2_2") (pintype "passive"))
      (node (ref "R30") (pin "2") (pinfunction "2_2") (pintype "passive"))
      (node (ref "R31") (pin "2") (pinfunction "2_2") (pintype "passive"))
      (node (ref "R9") (pin "1") (pinfunction "1_1") (pintype "passive"))
      (node (ref "U$1") (pin "P$10") (pinfunction "10VDD_P$10") (pintype "bidirectional"))
      (node (ref "U$1") (pin "P$19") (pinfunction "19AVDD_P$19") (pintype "bidirectional"))
      (node (ref "U$1") (pin "P$26") (pinfunction "26VDD_P$26") (pintype "bidirectional"))
      (node (ref "U$1") (pin "P$35") (pinfunction "35VUSB_P$35") (pintype "bidirectional"))
      (node (ref "U$1") (pin "P$38") (pinfunction "38VDD_P$38") (pintype "bidirectional"))
      (node (ref "U$1") (pin "P$57") (pinfunction "57VDD_P$57") (pintype "bidirectional"))
      (node (ref "U$14_LM3671MF-2.8") (pin "P$1") (pinfunction "VIN_P$1") (pintype "bidirectional"))
      (node (ref "U$16_LM3671MF-1.8") (pin "P$1") (pinfunction "VIN_P$1") (pintype "bidirectional"))
      (node (ref "U$17_LM3671-1.5") (pin "P$1") (pinfunction "VIN_P$1") (pintype "bidirectional"))
      (node (ref "U$2") (pin "1") (pinfunction "VDD_1") (pintype "power_in"))
      (node (ref "U$5_LM3671MF-3.3") (pin "P$4") (pinfunction "FB_P$4") (pintype "bidirectional"))
      (node (ref "U$6") (pin "P$4") (pinfunction "VIN_P$4") (pintype "bidirectional"))
      (node (ref "U$9") (pin "P$4") (pinfunction "VIN_P$4") (pintype "bidirectional"))
    )
    (net (code "33") (name "5V") (class "Default")
      (node (ref "C15") (pin "1") (pinfunction "1_1") (pintype "passive"))
      (node (ref "U$15") (pin "P$5") (pinfunction "P$3_P$5") (pintype "bidirectional"))
      (node (ref "U$5_LM3671MF-3.3") (pin "P$1") (pinfunction "VIN_P$1") (pintype "bidirectional"))
      (node (ref "U$5_LM3671MF-3.3") (pin "P$3") (pinfunction "EN_P$3") (pintype "bidirectional"))
    )
    (net (code "34") (name "GND") (class "Default")
      (node (ref "C1") (pin "2") (pinfunction "2_2") (pintype "passive"))
      (node (ref "C10") (pin "2") (pinfunction "2_2") (pintype "passive"))
      (node (ref "C11") (pin "2") (pinfunction "2_2") (pintype "passive"))
      (node (ref "C12") (pin "2") (pinfunction "2_2") (pintype "passive"))
      (node (ref "C13") (pin "C") (pinfunction "-_C") (pintype "passive"))
      (node (ref "C14") (pin "C") (pinfunction "-_C") (pintype "passive"))
      (node (ref "C15") (pin "2") (pinfunction "2_2") (pintype "passive"))
      (node (ref "C16") (pin "2") (pinfunction "2_2") (pintype "passive"))
      (node (ref "C17") (pin "C") (pinfunction "-_C") (pintype "passive"))
      (node (ref "C2") (pin "2") (pinfunction "2_2") (pintype "passive"))
      (node (ref "C20") (pin "1") (pinfunction "1_1") (pintype "passive"))
      (node (ref "C21") (pin "1") (pinfunction "1_1") (pintype "passive"))
      (node (ref "C22") (pin "2") (pinfunction "2_2") (pintype "passive"))
      (node (ref "C23") (pin "2") (pinfunction "2_2") (pintype "passive"))
      (node (ref "C24") (pin "2") (pinfunction "2_2") (pintype "passive"))
      (node (ref "C25") (pin "2") (pinfunction "2_2") (pintype "passive"))
      (node (ref "C26") (pin "2") (pinfunction "2_2") (pintype "passive"))
      (node (ref "C27") (pin "2") (pinfunction "2_2") (pintype "passive"))
      (node (ref "C28") (pin "2") (pinfunction "2_2") (pintype "passive"))
      (node (ref "C29") (pin "2") (pinfunction "2_2") (pintype "passive"))
      (node (ref "C3") (pin "2") (pinfunction "2_2") (pintype "passive"))
      (node (ref "C30") (pin "2") (pinfunction "2_2") (pintype "passive"))
      (node (ref "C31") (pin "C") (pinfunction "-_C") (pintype "passive"))
      (node (ref "C32") (pin "2") (pinfunction "2_2") (pintype "passive"))
      (node (ref "C33") (pin "2") (pinfunction "2_2") (pintype "passive"))
      (node (ref "C34") (pin "2") (pinfunction "2_2") (pintype "passive"))
      (node (ref "C35") (pin "2") (pinfunction "2_2") (pintype "passive"))
      (node (ref "C36") (pin "2") (pinfunction "2_2") (pintype "passive"))
      (node (ref "C37") (pin "2") (pinfunction "2_2") (pintype "passive"))
      (node (ref "C38") (pin "2") (pinfunction "2_2") (pintype "passive"))
      (node (ref "C39") (pin "2") (pinfunction "2_2") (pintype "passive"))
      (node (ref "C4") (pin "2") (pinfunction "2_2") (pintype "passive"))
      (node (ref "C40") (pin "1") (pinfunction "1_1") (pintype "passive"))
      (node (ref "C41") (pin "1") (pinfunction "1_1") (pintype "passive"))
      (node (ref "C42") (pin "1") (pinfunction "1_1") (pintype "passive"))
      (node (ref "C43") (pin "1") (pinfunction "1_1") (pintype "passive"))
      (node (ref "C44") (pin "1") (pinfunction "1_1") (pintype "passive"))
      (node (ref "C45") (pin "1") (pinfunction "1_1") (pintype "passive"))
      (node (ref "C46") (pin "2") (pinfunction "2_2") (pintype "passive"))
      (node (ref "C47") (pin "1") (pinfunction "1_1") (pintype "passive"))
      (node (ref "C48") (pin "1") (pinfunction "1_1") (pintype "passive"))
      (node (ref "C49") (pin "1") (pinfunction "1_1") (pintype "passive"))
      (node (ref "C5") (pin "2") (pinfunction "2_2") (pintype "passive"))
      (node (ref "C50") (pin "1") (pinfunction "1_1") (pintype "passive"))
      (node (ref "C51") (pin "1") (pinfunction "1_1") (pintype "passive"))
      (node (ref "C52") (pin "1") (pinfunction "1_1") (pintype "passive"))
      (node (ref "C53") (pin "C") (pinfunction "-_C") (pintype "passive"))
      (node (ref "C54") (pin "2") (pinfunction "2_2") (pintype "passive"))
      (node (ref "C55") (pin "2") (pinfunction "2_2") (pintype "passive"))
      (node (ref "C56") (pin "2") (pinfunction "2_2") (pintype "passive"))
      (node (ref "C57") (pin "2") (pinfunction "2_2") (pintype "passive"))
      (node (ref "C58") (pin "2") (pinfunction "2_2") (pintype "passive"))
      (node (ref "C59") (pin "C") (pinfunction "-_C") (pintype "passive"))
      (node (ref "C6") (pin "A") (pinfunction "+_A") (pintype "passive"))
      (node (ref "C60") (pin "C") (pinfunction "-_C") (pintype "passive"))
      (node (ref "C61") (pin "1") (pinfunction "1_1") (pintype "passive"))
      (node (ref "C62") (pin "1") (pinfunction "1_1") (pintype "passive"))
      (node (ref "C63") (pin "1") (pinfunction "1_1") (pintype "passive"))
      (node (ref "C7") (pin "2") (pinfunction "2_2") (pintype "passive"))
      (node (ref "C8") (pin "2") (pinfunction "2_2") (pintype "passive"))
      (node (ref "C9") (pin "2") (pinfunction "2_2") (pintype "passive"))
      (node (ref "CAM1") (pin "15") (pinfunction "IOVSS_15") (pintype "power_in"))
      (node (ref "CAM1") (pin "7") (pinfunction "DVSS_7") (pintype "power_in"))
      (node (ref "CON1") (pin "10") (pinfunction "10_10") (pintype "passive"))
      (node (ref "CON1") (pin "12") (pinfunction "12_12") (pintype "passive"))
      (node (ref "CON1") (pin "14") (pinfunction "14_14") (pintype "passive"))
      (node (ref "CON1") (pin "16") (pinfunction "16_16") (pintype "passive"))
      (node (ref "CON1") (pin "18") (pinfunction "18_18") (pintype "passive"))
      (node (ref "CON1") (pin "20") (pinfunction "20_20") (pintype "passive"))
      (node (ref "CON1") (pin "4") (pinfunction "4_4") (pintype "passive"))
      (node (ref "CON1") (pin "6") (pinfunction "6_6") (pintype "passive"))
      (node (ref "CON1") (pin "8") (pinfunction "8_8") (pintype "passive"))
      (node (ref "IC1") (pin "15") (pinfunction "GND_15") (pintype "power_in"))
      (node (ref "IC3") (pin "11") (pinfunction "V-_11") (pintype "power_in"))
      (node (ref "J1") (pin "3") (pinfunction "3_3") (pintype "passive"))
      (node (ref "J2") (pin "GND") (pinfunction "GNDBREAK_GND") (pintype "bidirectional"))
      (node (ref "J2") (pin "P$4") (pinfunction "GND_P$4") (pintype "bidirectional"))
      (node (ref "JP4_ITG-3200") (pin "3") (pinfunction "3_3") (pintype "passive"))
      (node (ref "JP5_MMA8452Q") (pin "6") (pinfunction "6_6") (pintype "passive"))
      (node (ref "JP6") (pin "1") (pinfunction "1_1") (pintype "passive"))
      (node (ref "JP6_MAG3110") (pin "2") (pinfunction "2_2") (pintype "passive"))
      (node (ref "LED1") (pin "C") (pinfunction "C_C") (pintype "passive"))
      (node (ref "LED2") (pin "C") (pinfunction "C_C") (pintype "passive"))
      (node (ref "R21") (pin "1") (pinfunction "1_1") (pintype "passive"))
      (node (ref "R23") (pin "1") (pinfunction "1_1") (pintype "passive"))
      (node (ref "S1") (pin "3") (pinfunction "3_3") (pintype "passive"))
      (node (ref "S1") (pin "4") (pinfunction "4_4") (pintype "passive"))
      (node (ref "S4") (pin "1") (pinfunction "1_1") (pintype "passive"))
      (node (ref "S4") (pin "2") (pinfunction "2_2") (pintype "passive"))
      (node (ref "U$1") (pin "P$20") (pinfunction "20AVSS_P$20") (pintype "bidirectional"))
      (node (ref "U$1") (pin "P$25") (pinfunction "25VSS_P$25") (pintype "bidirectional"))
      (node (ref "U$1") (pin "P$41") (pinfunction "41VSS_P$41") (pintype "bidirectional"))
      (node (ref "U$1") (pin "P$9") (pinfunction "9VSS_P$9") (pintype "bidirectional"))
      (node (ref "U$14_LM3671MF-2.8") (pin "P$2") (pinfunction "GND_P$2") (pintype "bidirectional"))
      (node (ref "U$16_LM3671MF-1.8") (pin "P$2") (pinfunction "GND_P$2") (pintype "bidirectional"))
      (node (ref "U$17_LM3671-1.5") (pin "P$2") (pinfunction "GND_P$2") (pintype "bidirectional"))
      (node (ref "U$2") (pin "10") (pinfunction "GND_10") (pintype "power_in"))
      (node (ref "U$5") (pin "P$1") (pinfunction "1_P$1") (pintype "bidirectional"))
      (node (ref "U$5_LM3671MF-3.3") (pin "P$2") (pinfunction "GND_P$2") (pintype "bidirectional"))
      (node (ref "U$6") (pin "P$2") (pinfunction "2GND_P$2") (pintype "bidirectional"))
      (node (ref "U$6") (pin "P$5") (pinfunction "5GND_P$5") (pintype "bidirectional"))
      (node (ref "U$7") (pin "113") (pinfunction "GND(10)_113") (pintype "bidirectional"))
      (node (ref "U$7") (pin "133") (pinfunction "GND(11)_133") (pintype "bidirectional"))
      (node (ref "U$7") (pin "14") (pinfunction "GND(2)_14") (pintype "bidirectional"))
      (node (ref "U$7") (pin "146") (pinfunction "GND(12)_146") (pintype "bidirectional"))
      (node (ref "U$7") (pin "151") (pinfunction "GNDPLL(1)_151") (pintype "bidirectional"))
      (node (ref "U$7") (pin "153") (pinfunction "GNDPLL(2)_153") (pintype "bidirectional"))
      (node (ref "U$7") (pin "156") (pinfunction "GNDANA_156") (pintype "bidirectional"))
      (node (ref "U$7") (pin "170") (pinfunction "GND(13)_170") (pintype "bidirectional"))
      (node (ref "U$7") (pin "173") (pinfunction "GND(14)_173") (pintype "bidirectional"))
      (node (ref "U$7") (pin "188") (pinfunction "GND(15)_188") (pintype "bidirectional"))
      (node (ref "U$7") (pin "200") (pinfunction "GND(16)_200") (pintype "bidirectional"))
      (node (ref "U$7") (pin "204") (pinfunction "GND(17)_204") (pintype "bidirectional"))
      (node (ref "U$7") (pin "25") (pinfunction "GND(3)_25") (pintype "bidirectional"))
      (node (ref "U$7") (pin "33") (pinfunction "GND_33") (pintype "bidirectional"))
      (node (ref "U$7") (pin "39") (pinfunction "GND(5)_39") (pintype "bidirectional"))
      (node (ref "U$7") (pin "40") (pinfunction "ERASE_40") (pintype "bidirectional"))
      (node (ref "U$7") (pin "41") (pinfunction "OSCSEL_41") (pintype "bidirectional"))
      (node (ref "U$7") (pin "42") (pinfunction "TST_42") (pintype "bidirectional"))
      (node (ref "U$7") (pin "43") (pinfunction "JTAGSEL_43") (pintype "bidirectional"))
      (node (ref "U$7") (pin "44") (pinfunction "GNDBU_44") (pintype "bidirectional"))
      (node (ref "U$7") (pin "50") (pinfunction "HDMA_50") (pintype "bidirectional"))
      (node (ref "U$7") (pin "51") (pinfunction "HDPA_51") (pintype "bidirectional"))
      (node (ref "U$7") (pin "53") (pinfunction "GND(6)_53") (pintype "bidirectional"))
      (node (ref "U$7") (pin "54") (pinfunction "DDM_54") (pintype "bidirectional"))
      (node (ref "U$7") (pin "55") (pinfunction "DDP_55") (pintype "bidirectional"))
      (node (ref "U$7") (pin "6") (pinfunction "GND(1)_6") (pintype "bidirectional"))
      (node (ref "U$7") (pin "66") (pinfunction "GND(7)_66") (pintype "bidirectional"))
      (node (ref "U$7") (pin "78") (pinfunction "GND(8)_78") (pintype "bidirectional"))
      (node (ref "U$7") (pin "91") (pinfunction "GND(9)_91") (pintype "bidirectional"))
      (node (ref "U$9") (pin "P$2") (pinfunction "2GND_P$2") (pintype "bidirectional"))
      (node (ref "U$9") (pin "P$5") (pinfunction "5GND_P$5") (pintype "bidirectional"))
      (node (ref "X2") (pin "GND") (pinfunction "GND_GND") (pintype "bidirectional"))
    )
    (net (code "35") (name "Net-(C1-Pad1)") (class "Default")
      (node (ref "C1") (pin "1") (pinfunction "1_1") (pintype "passive"))
      (node (ref "R1") (pin "1") (pinfunction "1_1") (pintype "passive"))
      (node (ref "R2") (pin "1") (pinfunction "1_1") (pintype "passive"))
      (node (ref "S4") (pin "3") (pinfunction "3_3") (pintype "passive"))
      (node (ref "S4") (pin "4") (pinfunction "4_4") (pintype "passive"))
    )
    (net (code "36") (name "Net-(C6--)") (class "Default")
      (node (ref "C6") (pin "C") (pinfunction "-_C") (pintype "passive"))
      (node (ref "IC1") (pin "6") (pinfunction "V-_6") (pintype "bidirectional"))
    )
    (net (code "37") (name "Net-(C13-+)") (class "Default")
      (node (ref "C13") (pin "A") (pinfunction "+_A") (pintype "passive"))
      (node (ref "C5") (pin "1") (pinfunction "1_1") (pintype "passive"))
      (node (ref "U$1") (pin "P$56") (pinfunction "56VCAP/VCORE_P$56") (pintype "bidirectional"))
    )
    (net (code "38") (name "Net-(C14-+)") (class "Default")
      (node (ref "C14") (pin "A") (pinfunction "+_A") (pintype "passive"))
      (node (ref "IC1") (pin "2") (pinfunction "V+_2") (pintype "bidirectional"))
    )
    (net (code "39") (name "Net-(C18-+)") (class "Default")
      (node (ref "C18") (pin "A") (pinfunction "+_A") (pintype "passive"))
      (node (ref "IC1") (pin "1") (pinfunction "C1+_1") (pintype "bidirectional"))
    )
    (net (code "40") (name "Net-(C18--)") (class "Default")
      (node (ref "C18") (pin "C") (pinfunction "-_C") (pintype "passive"))
      (node (ref "IC1") (pin "3") (pinfunction "C1-_3") (pintype "bidirectional"))
    )
    (net (code "41") (name "Net-(C19-+)") (class "Default")
      (node (ref "C19") (pin "A") (pinfunction "+_A") (pintype "passive"))
      (node (ref "IC1") (pin "4") (pinfunction "C2+_4") (pintype "bidirectional"))
    )
    (net (code "42") (name "Net-(C19--)") (class "Default")
      (node (ref "C19") (pin "C") (pinfunction "-_C") (pintype "passive"))
      (node (ref "IC1") (pin "5") (pinfunction "C2-_5") (pintype "bidirectional"))
    )
    (net (code "43") (name "Net-(C29-Pad1)") (class "Default")
      (node (ref "C29") (pin "1") (pinfunction "1_1") (pintype "passive"))
      (node (ref "R18") (pin "2") (pinfunction "2_2") (pintype "passive"))
    )
    (net (code "44") (name "Net-(C31-+)") (class "Default")
      (node (ref "C24") (pin "1") (pinfunction "1_1") (pintype "passive"))
      (node (ref "C25") (pin "1") (pinfunction "1_1") (pintype "passive"))
      (node (ref "C26") (pin "1") (pinfunction "1_1") (pintype "passive"))
      (node (ref "C27") (pin "1") (pinfunction "1_1") (pintype "passive"))
      (node (ref "C30") (pin "1") (pinfunction "1_1") (pintype "passive"))
      (node (ref "C31") (pin "A") (pinfunction "+_A") (pintype "passive"))
      (node (ref "C32") (pin "1") (pinfunction "1_1") (pintype "passive"))
      (node (ref "C34") (pin "1") (pinfunction "1_1") (pintype "passive"))
      (node (ref "C35") (pin "1") (pinfunction "1_1") (pintype "passive"))
      (node (ref "C36") (pin "1") (pinfunction "1_1") (pintype "passive"))
      (node (ref "C40") (pin "2") (pinfunction "2_2") (pintype "passive"))
      (node (ref "C41") (pin "2") (pinfunction "2_2") (pintype "passive"))
      (node (ref "C43") (pin "2") (pinfunction "2_2") (pintype "passive"))
      (node (ref "C44") (pin "2") (pinfunction "2_2") (pintype "passive"))
      (node (ref "R14") (pin "2") (pinfunction "2_2") (pintype "passive"))
      (node (ref "R15") (pin "2") (pinfunction "2_2") (pintype "passive"))
      (node (ref "R16") (pin "2") (pinfunction "2_2") (pintype "passive"))
      (node (ref "U$6") (pin "P$1") (pinfunction "VOUT_P$1") (pintype "bidirectional"))
      (node (ref "U$7") (pin "114") (pinfunction "VDDIOM(3)_114") (pintype "bidirectional"))
      (node (ref "U$7") (pin "13") (pinfunction "VDDIOP0(2)_13") (pintype "bidirectional"))
      (node (ref "U$7") (pin "132") (pinfunction "VDDIOM(4)_132") (pintype "bidirectional"))
      (node (ref "U$7") (pin "160") (pinfunction "VDDANA_160") (pintype "bidirectional"))
      (node (ref "U$7") (pin "169") (pinfunction "VDDIOP1_169") (pintype "bidirectional"))
      (node (ref "U$7") (pin "187") (pinfunction "VDDIOP0(6)_187") (pintype "bidirectional"))
      (node (ref "U$7") (pin "199") (pinfunction "VDDIOP0(7)_199") (pintype "bidirectional"))
      (node (ref "U$7") (pin "24") (pinfunction "VDDIOP0(3)_24") (pintype "bidirectional"))
      (node (ref "U$7") (pin "32") (pinfunction "VDDIOP0(4)_32") (pintype "bidirectional"))
      (node (ref "U$7") (pin "5") (pinfunction "VDDIOP0(1)_5") (pintype "bidirectional"))
      (node (ref "U$7") (pin "52") (pinfunction "VDDIOP0(5)_52") (pintype "bidirectional"))
      (node (ref "U$7") (pin "65") (pinfunction "VDDIOM(1)_65") (pintype "bidirectional"))
      (node (ref "U$7") (pin "90") (pinfunction "VDDIOM(2)_90") (pintype "bidirectional"))
    )
    (net (code "45") (name "Net-(C60-+)") (class "Default")
      (node (ref "C58") (pin "1") (pinfunction "1_1") (pintype "passive"))
      (node (ref "C60") (pin "A") (pinfunction "+_A") (pintype "passive"))
      (node (ref "IC3") (pin "10") (pinfunction "GND_10") (pintype "power_in"))
      (node (ref "IC3") (pin "12") (pinfunction "FCB_12") (pintype "passive"))
      (node (ref "IC3") (pin "17") (pinfunction "GND_17") (pintype "power_in"))
      (node (ref "IC3") (pin "3") (pinfunction "GND_3") (pintype "power_in"))
      (node (ref "IC3") (pin "5") (pinfunction "GND_5") (pintype "power_in"))
      (node (ref "IC3") (pin "9") (pinfunction "FCA_9") (pintype "passive"))
      (node (ref "R20") (pin "1") (pinfunction "1_1") (pintype "passive"))
      (node (ref "R21") (pin "2") (pinfunction "2_2") (pintype "passive"))
    )
    (net (code "46") (name "Net-(CAM1-DCLK)") (class "Default")
      (node (ref "CAM1") (pin "10") (pinfunction "DCLK_10") (pintype "output"))
      (node (ref "U$7") (pin "175") (pinfunction "PB28_175") (pintype "bidirectional"))
    )
    (net (code "47") (name "Net-(CAM1-DOUT0)") (class "Default")
      (node (ref "CAM1") (pin "11") (pinfunction "DOUT0_11") (pintype "output"))
      (node (ref "U$7") (pin "163") (pinfunction "PB20_163") (pintype "bidirectional"))
    )
    (net (code "48") (name "Net-(CAM1-DOUT1)") (class "Default")
      (node (ref "CAM1") (pin "12") (pinfunction "DOUT1_12") (pintype "output"))
      (node (ref "U$7") (pin "164") (pinfunction "PB21_164") (pintype "bidirectional"))
    )
    (net (code "49") (name "Net-(CAM1-DOUT2)") (class "Default")
      (node (ref "CAM1") (pin "13") (pinfunction "DOUT2_13") (pintype "output"))
      (node (ref "U$7") (pin "165") (pinfunction "PB22_165") (pintype "bidirectional"))
    )
    (net (code "50") (name "Net-(CAM1-DOUT3)") (class "Default")
      (node (ref "CAM1") (pin "14") (pinfunction "DOUT3_14") (pintype "output"))
      (node (ref "U$7") (pin "166") (pinfunction "PB23_166") (pintype "bidirectional"))
    )
    (net (code "51") (name "Net-(CAM1-DOUT4)") (class "Default")
      (node (ref "CAM1") (pin "17") (pinfunction "DOUT4_17") (pintype "output"))
      (node (ref "U$7") (pin "167") (pinfunction "PB24_167") (pintype "bidirectional"))
    )
    (net (code "52") (name "Net-(CAM1-DOUT5)") (class "Default")
      (node (ref "CAM1") (pin "18") (pinfunction "DOUT5_18") (pintype "output"))
      (node (ref "U$7") (pin "168") (pinfunction "PB25_168") (pintype "bidirectional"))
    )
    (net (code "53") (name "Net-(CAM1-DOUT6)") (class "Default")
      (node (ref "CAM1") (pin "19") (pinfunction "DOUT6_19") (pintype "output"))
      (node (ref "U$7") (pin "171") (pinfunction "PB26_171") (pintype "bidirectional"))
    )
    (net (code "54") (name "Net-(CAM1-DOUT7)") (class "Default")
      (node (ref "CAM1") (pin "20") (pinfunction "DOUT7_20") (pintype "output"))
      (node (ref "U$7") (pin "172") (pinfunction "PB27_172") (pintype "bidirectional"))
    )
    (net (code "55") (name "Net-(CAM1-EXTCLK)") (class "Default")
      (node (ref "CAM1") (pin "2") (pinfunction "EXTCLK_2") (pintype "input"))
      (node (ref "U$7") (pin "178") (pinfunction "PB31_178") (pintype "bidirectional"))
    )
    (net (code "56") (name "Net-(CAM1-HD)") (class "Default")
      (node (ref "CAM1") (pin "9") (pinfunction "HD_9") (pintype "output"))
      (node (ref "U$7") (pin "177") (pinfunction "PB30_177") (pintype "bidirectional"))
    )
    (net (code "57") (name "Net-(CAM1-IOVDD)") (class "Default")
      (node (ref "CAM1") (pin "1") (pinfunction "PVDD_1") (pintype "power_in"))
      (node (ref "CAM1") (pin "16") (pinfunction "IOVDD_16") (pintype "power_in"))
      (node (ref "R33") (pin "2") (pinfunction "2_2") (pintype "passive"))
      (node (ref "R34") (pin "2") (pinfunction "2_2") (pintype "passive"))
      (node (ref "SJ1") (pin "1") (pinfunction "1_1") (pintype "passive"))
      (node (ref "SJ2") (pin "1") (pinfunction "1_1") (pintype "passive"))
    )
    (net (code "58") (name "Net-(CAM1-RESET)") (class "Default")
      (node (ref "CAM1") (pin "3") (pinfunction "RESET_3") (pintype "input"))
      (node (ref "R25") (pin "1") (pinfunction "1_1") (pintype "passive"))
    )
    (net (code "59") (name "Net-(CAM1-SCL)") (class "Default")
      (node (ref "CAM1") (pin "4") (pinfunction "SCL_4") (pintype "input"))
      (node (ref "R34") (pin "1") (pinfunction "1_1") (pintype "passive"))
      (node (ref "U$7") (pin "1") (pinfunction "PA24_1") (pintype "bidirectional"))
    )
    (net (code "60") (name "Net-(CAM1-SDA)") (class "Default")
      (node (ref "CAM1") (pin "5") (pinfunction "SDA_5") (pintype "bidirectional"))
      (node (ref "R33") (pin "1") (pinfunction "1_1") (pintype "passive"))
      (node (ref "U$7") (pin "208") (pinfunction "PA23_208") (pintype "bidirectional"))
    )
    (net (code "61") (name "Net-(CAM1-VD)") (class "Default")
      (node (ref "CAM1") (pin "8") (pinfunction "VD_8") (pintype "output"))
      (node (ref "U$7") (pin "176") (pinfunction "PB29_176") (pintype "bidirectional"))
    )
    (net (code "62") (name "Net-(IC1A-R1OUT)") (class "Default")
      (node (ref "IC1") (pin "12") (pinfunction "R1OUT_12") (pintype "output"))
      (node (ref "R22") (pin "2") (pinfunction "2_2") (pintype "passive"))
    )
    (net (code "63") (name "Net-(IC1A-R2OUT)") (class "Default")
      (node (ref "IC1") (pin "9") (pinfunction "R2OUT_9") (pintype "output"))
      (node (ref "R24") (pin "2") (pinfunction "2_2") (pintype "passive"))
    )
    (net (code "64") (name "Net-(IC3-BPIA)") (class "Default")
      (node (ref "IC3") (pin "7") (pinfunction "BPIA_7") (pintype "input"))
      (node (ref "R13") (pin "2") (pinfunction "2_2") (pintype "passive"))
    )
    (net (code "65") (name "Net-(IC3-BPIB)") (class "Default")
      (node (ref "IC3") (pin "15") (pinfunction "BPIB_15") (pintype "input"))
      (node (ref "R8") (pin "1") (pinfunction "1_1") (pintype "passive"))
    )
    (net (code "66") (name "Net-(IC3-BPOA)") (class "Default")
      (node (ref "IC3") (pin "4") (pinfunction "BPOA_4") (pintype "output"))
      (node (ref "R11") (pin "1") (pinfunction "1_1") (pintype "passive"))
      (node (ref "R12") (pin "1") (pinfunction "1_1") (pintype "passive"))
      (node (ref "R5") (pin "2") (pinfunction "2_2") (pintype "passive"))
    )
    (net (code "67") (name "Net-(IC3-INA)") (class "Default")
      (node (ref "IC3") (pin "8") (pinfunction "INA_8") (pintype "input"))
      (node (ref "R10") (pin "2") (pinfunction "2_2") (pintype "passive"))
      (node (ref "R11") (pin "2") (pinfunction "2_2") (pintype "passive"))
    )
    (net (code "68") (name "Net-(IC3-INB)") (class "Default")
      (node (ref "IC3") (pin "14") (pinfunction "INB_14") (pintype "input"))
      (node (ref "R5") (pin "1") (pinfunction "1_1") (pintype "passive"))
      (node (ref "R6") (pin "1") (pinfunction "1_1") (pintype "passive"))
    )
    (net (code "69") (name "Net-(IC3-LPIA)") (class "Default")
      (node (ref "IC3") (pin "6") (pinfunction "LPIA_6") (pintype "input"))
      (node (ref "R12") (pin "2") (pinfunction "2_2") (pintype "passive"))
    )
    (net (code "70") (name "Net-(IC3-LPIB)") (class "Default")
      (node (ref "IC3") (pin "16") (pinfunction "LPIB_16") (pintype "input"))
      (node (ref "R7") (pin "1") (pinfunction "1_1") (pintype "passive"))
    )
    (net (code "71") (name "Net-(IC3-LPOA)") (class "Default")
      (node (ref "IC3") (pin "2") (pinfunction "LPOA_2") (pintype "output"))
      (node (ref "R13") (pin "1") (pinfunction "1_1") (pintype "passive"))
    )
    (net (code "72") (name "Net-(IC3-LPOB)") (class "Default")
      (node (ref "IC3") (pin "19") (pinfunction "LPOB_19") (pintype "output"))
      (node (ref "R8") (pin "2") (pinfunction "2_2") (pintype "passive"))
    )
    (net (code "73") (name "Net-(J1-Pad1)") (class "Default")
      (node (ref "J1") (pin "1") (pinfunction "1_1") (pintype "passive"))
      (node (ref "R1") (pin "2") (pinfunction "2_2") (pintype "passive"))
      (node (ref "R4") (pin "1") (pinfunction "1_1") (pintype "passive"))
    )
    (net (code "74") (name "Net-(J2-PWR)") (class "Default")
      (node (ref "J2") (pin "VIN0") (pinfunction "PWR_VIN0") (pintype "bidirectional"))
      (node (ref "U$15") (pin "P$1") (pinfunction "P$1_P$1") (pintype "bidirectional"))
    )
    (net (code "75") (name "Net-(LED1-PadA)") (class "Default")
      (node (ref "LED1") (pin "A") (pinfunction "A_A") (pintype "passive"))
      (node (ref "R9") (pin "2") (pinfunction "2_2") (pintype "passive"))
    )
    (net (code "76") (name "Net-(LED2-PadA)") (class "Default")
      (node (ref "LED2") (pin "A") (pinfunction "A_A") (pintype "passive"))
      (node (ref "R32") (pin "2") (pinfunction "2_2") (pintype "passive"))
    )
    (net (code "77") (name "Net-(R23-Pad2)") (class "Default")
      (node (ref "R23") (pin "2") (pinfunction "2_2") (pintype "passive"))
      (node (ref "X1") (pin "5") (pinfunction "5_5") (pintype "passive"))
    )
    (net (code "78") (name "Net-(U$1-4U3RTS_L)") (class "Default")
      (node (ref "U$1") (pin "P$4") (pinfunction "4U3RTS_L_P$4") (pintype "bidirectional"))
      (node (ref "U$2") (pin "12") (pinfunction "CTS_12") (pintype "output"))
    )
    (net (code "79") (name "Net-(U$1-5U3RX)") (class "Default")
      (node (ref "U$1") (pin "P$5") (pinfunction "5U3RX_P$5") (pintype "bidirectional"))
      (node (ref "U$2") (pin "2") (pinfunction "DOUT_2") (pintype "output"))
    )
    (net (code "80") (name "Net-(U$1-6U3TX)") (class "Default")
      (node (ref "U$1") (pin "P$6") (pinfunction "6U3TX_P$6") (pintype "bidirectional"))
      (node (ref "U$2") (pin "3") (pinfunction "DIN_3") (pintype "input"))
    )
    (net (code "81") (name "Net-(U$1-7MCLR_L)") (class "Default")
      (node (ref "R4") (pin "2") (pinfunction "2_2") (pintype "passive"))
      (node (ref "U$1") (pin "P$7") (pinfunction "7MCLR_L_P$7") (pintype "bidirectional"))
    )
    (net (code "82") (name "Net-(U$1-8U3CTS_L)") (class "Default")
      (node (ref "U$1") (pin "P$8") (pinfunction "8U3CTS_L_P$8") (pintype "bidirectional"))
      (node (ref "U$2") (pin "16") (pinfunction "RTS_16") (pintype "input"))
    )
    (net (code "83") (name "Net-(U$1-17PGEC2)") (class "Default")
      (node (ref "J1") (pin "5") (pinfunction "5_5") (pintype "passive"))
      (node (ref "U$1") (pin "P$17") (pinfunction "17PGEC2_P$17") (pintype "bidirectional"))
    )
    (net (code "84") (name "Net-(U$1-18PGED2)") (class "Default")
      (node (ref "J1") (pin "4") (pinfunction "4_4") (pintype "passive"))
      (node (ref "U$1") (pin "P$18") (pinfunction "18PGED2_P$18") (pintype "bidirectional"))
    )
    (net (code "85") (name "Net-(U$1-36D-)") (class "Default")
      (node (ref "U$1") (pin "P$36") (pinfunction "36D-_P$36") (pintype "bidirectional"))
      (node (ref "X2") (pin "D-") (pinfunction "D-_D-") (pintype "bidirectional"))
    )
    (net (code "86") (name "Net-(U$1-37D+)") (class "Default")
      (node (ref "U$1") (pin "P$37") (pinfunction "37D+_P$37") (pintype "bidirectional"))
      (node (ref "X2") (pin "D+") (pinfunction "D+_D+") (pintype "bidirectional"))
    )
    (net (code "87") (name "Net-(U$1-39OSC1{slash}CLKI)") (class "Default")
      (node (ref "C8") (pin "1") (pinfunction "1_1") (pintype "passive"))
      (node (ref "Q1") (pin "2") (pinfunction "2_2") (pintype "passive"))
      (node (ref "U$1") (pin "P$39") (pinfunction "39OSC1/CLKI_P$39") (pintype "bidirectional"))
    )
    (net (code "88") (name "Net-(U$1-40OSC2{slash}CLKO)") (class "Default")
      (node (ref "C9") (pin "1") (pinfunction "1_1") (pintype "passive"))
      (node (ref "Q1") (pin "1") (pinfunction "1_1") (pintype "passive"))
      (node (ref "U$1") (pin "P$40") (pinfunction "40OSC2/CLKO_P$40") (pintype "bidirectional"))
    )
    (net (code "89") (name "Net-(U$5-2)") (class "Default")
      (node (ref "R10") (pin "1") (pinfunction "1_1") (pintype "passive"))
      (node (ref "U$5") (pin "P$2") (pinfunction "2_P$2") (pintype "bidirectional"))
    )
    (net (code "90") (name "Net-(U$5_LM3671MF-3.3-SW)") (class "Default")
      (node (ref "L4") (pin "1") (pinfunction "1_1") (pintype "passive"))
      (node (ref "U$5_LM3671MF-3.3") (pin "P$5") (pinfunction "SW_P$5") (pintype "bidirectional"))
    )
    (net (code "91") (name "Net-(U$7-NRST)") (class "Default")
      (node (ref "CON1") (pin "15") (pinfunction "15_15") (pintype "passive"))
      (node (ref "R17") (pin "2") (pinfunction "2_2") (pintype "passive"))
      (node (ref "S1") (pin "1") (pinfunction "1_1") (pintype "passive"))
      (node (ref "S1") (pin "2") (pinfunction "2_2") (pintype "passive"))
      (node (ref "U$7") (pin "36") (pinfunction "NRST_36") (pintype "bidirectional"))
    )
    (net (code "92") (name "Net-(U$7-NTRST)") (class "Default")
      (node (ref "CON1") (pin "3") (pinfunction "3_3") (pintype "passive"))
      (node (ref "U$7") (pin "35") (pinfunction "NTRST_35") (pintype "bidirectional"))
    )
    (net (code "93") (name "Net-(U$7-PA25)") (class "Default")
      (node (ref "R32") (pin "1") (pinfunction "1_1") (pintype "passive"))
      (node (ref "U$7") (pin "2") (pinfunction "PA25_2") (pintype "bidirectional"))
    )
    (net (code "94") (name "Net-(U$7-PLLRCA)") (class "Default")
      (node (ref "C54") (pin "1") (pinfunction "1_1") (pintype "passive"))
      (node (ref "R18") (pin "1") (pinfunction "1_1") (pintype "passive"))
      (node (ref "U$7") (pin "154") (pinfunction "PLLRCA_154") (pintype "bidirectional"))
    )
    (net (code "95") (name "Net-(U$7-RTCK)") (class "Default")
      (node (ref "CON1") (pin "11") (pinfunction "11_11") (pintype "passive"))
      (node (ref "U$7") (pin "37") (pinfunction "RTCK_37") (pintype "bidirectional"))
    )
    (net (code "96") (name "Net-(U$7-SHDN)") (class "Default")
      (node (ref "R19") (pin "2") (pinfunction "2_2") (pintype "passive"))
      (node (ref "U$7") (pin "49") (pinfunction "SHDN_49") (pintype "bidirectional"))
    )
    (net (code "97") (name "Net-(U$7-TCK)") (class "Default")
      (node (ref "CON1") (pin "9") (pinfunction "9_9") (pintype "passive"))
      (node (ref "R16") (pin "1") (pinfunction "1_1") (pintype "passive"))
      (node (ref "U$7") (pin "34") (pinfunction "TCK_34") (pintype "bidirectional"))
    )
    (net (code "98") (name "Net-(U$7-TDI)") (class "Default")
      (node (ref "CON1") (pin "5") (pinfunction "5_5") (pintype "passive"))
      (node (ref "R14") (pin "1") (pinfunction "1_1") (pintype "passive"))
      (node (ref "U$7") (pin "30") (pinfunction "TDI_30") (pintype "bidirectional"))
    )
    (net (code "99") (name "Net-(U$7-TDO)") (class "Default")
      (node (ref "CON1") (pin "13") (pinfunction "13_13") (pintype "passive"))
      (node (ref "U$7") (pin "29") (pinfunction "TDO_29") (pintype "bidirectional"))
    )
    (net (code "100") (name "Net-(U$7-TMS)") (class "Default")
      (node (ref "CON1") (pin "7") (pinfunction "7_7") (pintype "passive"))
      (node (ref "R15") (pin "1") (pinfunction "1_1") (pintype "passive"))
      (node (ref "U$7") (pin "31") (pinfunction "TMS_31") (pintype "bidirectional"))
    )
    (net (code "101") (name "Net-(U$7-XIN)") (class "Default")
      (node (ref "300-8444-ND") (pin "1") (pinfunction "1_1") (pintype "passive"))
      (node (ref "C21") (pin "2") (pinfunction "2_2") (pintype "passive"))
      (node (ref "U$7") (pin "149") (pinfunction "XIN_149") (pintype "bidirectional"))
    )
    (net (code "102") (name "Net-(U$7-XIN32)") (class "Default")
      (node (ref "535-9034-ND") (pin "1") (pinfunction "1_1") (pintype "passive"))
      (node (ref "C22") (pin "1") (pinfunction "1_1") (pintype "passive"))
      (node (ref "C56") (pin "1") (pinfunction "1_1") (pintype "passive"))
      (node (ref "U$7") (pin "46") (pinfunction "XIN32_46") (pintype "bidirectional"))
    )
    (net (code "103") (name "Net-(U$7-XOUT)") (class "Default")
      (node (ref "300-8444-ND") (pin "2") (pinfunction "2_2") (pintype "passive"))
      (node (ref "C20") (pin "2") (pinfunction "2_2") (pintype "passive"))
      (node (ref "U$7") (pin "150") (pinfunction "XOUT_150") (pintype "bidirectional"))
    )
    (net (code "104") (name "Net-(U$7-XOUT32)") (class "Default")
      (node (ref "535-9034-ND") (pin "2") (pinfunction "2_2") (pintype "passive"))
      (node (ref "C23") (pin "1") (pinfunction "1_1") (pintype "passive"))
      (node (ref "C55") (pin "1") (pinfunction "1_1") (pintype "passive"))
      (node (ref "U$7") (pin "45") (pinfunction "XOUT32_45") (pintype "bidirectional"))
    )
    (net (code "105") (name "Net-(U$14_LM3671MF-2.8-SW)") (class "Default")
      (node (ref "L1") (pin "1") (pinfunction "1_1") (pintype "passive"))
      (node (ref "U$14_LM3671MF-2.8") (pin "P$5") (pinfunction "SW_P$5") (pintype "bidirectional"))
    )
    (net (code "106") (name "Net-(U$16_LM3671MF-1.8-SW)") (class "Default")
      (node (ref "L2") (pin "1") (pinfunction "1_1") (pintype "passive"))
      (node (ref "U$16_LM3671MF-1.8") (pin "P$5") (pinfunction "SW_P$5") (pintype "bidirectional"))
    )
    (net (code "107") (name "Net-(U$17_LM3671-1.5-SW)") (class "Default")
      (node (ref "L3") (pin "1") (pinfunction "1_1") (pintype "passive"))
      (node (ref "U$17_LM3671-1.5") (pin "P$5") (pinfunction "SW_P$5") (pintype "bidirectional"))
    )
    (net (code "108") (name "VCC") (class "Default")
      (node (ref "C52") (pin "2") (pinfunction "2_2") (pintype "passive"))
      (node (ref "CAM1") (pin "6") (pinfunction "DVDD_6") (pintype "power_in"))
      (node (ref "JP5") (pin "1") (pinfunction "1_1") (pintype "passive"))
      (node (ref "L3") (pin "2") (pinfunction "2_2") (pintype "passive"))
      (node (ref "U$17_LM3671-1.5") (pin "P$4") (pinfunction "FB_P$4") (pintype "bidirectional"))
    )
    (net (code "109") (name "unconnected-(CON1-Pad1)") (class "Default")
      (node (ref "CON1") (pin "1") (pinfunction "1_1") (pintype "passive"))
    )
    (net (code "110") (name "unconnected-(CON1-Pad2)") (class "Default")
      (node (ref "CON1") (pin "2") (pinfunction "2_2") (pintype "passive"))
    )
    (net (code "111") (name "unconnected-(CON1-Pad17)") (class "Default")
      (node (ref "CON1") (pin "17") (pinfunction "17_17") (pintype "passive"))
    )
    (net (code "112") (name "unconnected-(CON1-Pad19)") (class "Default")
      (node (ref "CON1") (pin "19") (pinfunction "19_19") (pintype "passive"))
    )
    (net (code "113") (name "unconnected-(J1-Pad6)") (class "Default")
      (node (ref "J1") (pin "6") (pinfunction "6_6") (pintype "passive"))
    )
    (net (code "114") (name "unconnected-(JP4_ITG-3200-Pad5)") (class "Default")
      (node (ref "JP4_ITG-3200") (pin "5") (pinfunction "5_5") (pintype "passive"))
    )
    (net (code "115") (name "unconnected-(JP5_MMA8452Q-Pad4)") (class "Default")
      (node (ref "JP5_MMA8452Q") (pin "4") (pinfunction "4_4") (pintype "passive"))
    )
    (net (code "116") (name "unconnected-(U$1-1PMD5{slash}RE5-PadP$1)") (class "Default")
      (node (ref "U$1") (pin "P$1") (pinfunction "1PMD5/RE5_P$1") (pintype "bidirectional"))
    )
    (net (code "117") (name "unconnected-(U$1-2PMD6{slash}RE6-PadP$2)") (class "Default")
      (node (ref "U$1") (pin "P$2") (pinfunction "2PMD6/RE6_P$2") (pintype "bidirectional"))
    )
    (net (code "118") (name "unconnected-(U$1-3PMD7{slash}RE7-PadP$3)") (class "Default")
      (node (ref "U$1") (pin "P$3") (pinfunction "3PMD7/RE7_P$3") (pintype "bidirectional"))
    )
    (net (code "119") (name "unconnected-(U$1-23TMS-PadP$23)") (class "Default")
      (node (ref "U$1") (pin "P$23") (pinfunction "23TMS_P$23") (pintype "bidirectional"))
    )
    (net (code "120") (name "unconnected-(U$1-24TDO-PadP$24)") (class "Default")
      (node (ref "U$1") (pin "P$24") (pinfunction "24TDO_P$24") (pintype "bidirectional"))
    )
    (net (code "121") (name "unconnected-(U$1-27TCK-PadP$27)") (class "Default")
      (node (ref "U$1") (pin "P$27") (pinfunction "27TCK_P$27") (pintype "bidirectional"))
    )
    (net (code "122") (name "unconnected-(U$1-28TDI-PadP$28)") (class "Default")
      (node (ref "U$1") (pin "P$28") (pinfunction "28TDI_P$28") (pintype "bidirectional"))
    )
    (net (code "123") (name "unconnected-(U$1-33USBID-PadP$33)") (class "Default")
      (node (ref "U$1") (pin "P$33") (pinfunction "33USBID_P$33") (pintype "bidirectional"))
    )
    (net (code "124") (name "unconnected-(U$1-47SOSCI-PadP$47)") (class "Default")
      (node (ref "U$1") (pin "P$47") (pinfunction "47SOSCI_P$47") (pintype "bidirectional"))
    )
    (net (code "125") (name "unconnected-(U$1-48SOSCO-PadP$48)") (class "Default")
      (node (ref "U$1") (pin "P$48") (pinfunction "48SOSCO_P$48") (pintype "bidirectional"))
    )
    (net (code "126") (name "unconnected-(U$1-PadP$22)") (class "Default")
      (node (ref "U$1") (pin "P$22") (pinfunction "P$22_P$22") (pintype "bidirectional"))
    )
    (net (code "127") (name "unconnected-(U$1-PadP$58)") (class "Default")
      (node (ref "U$1") (pin "P$58") (pinfunction "P$58_P$58") (pintype "bidirectional"))
    )
    (net (code "128") (name "unconnected-(U$1-PadP$59)") (class "Default")
      (node (ref "U$1") (pin "P$59") (pinfunction "P$59_P$59") (pintype "bidirectional"))
    )
    (net (code "129") (name "unconnected-(U$1-PadP$60)") (class "Default")
      (node (ref "U$1") (pin "P$60") (pinfunction "P$60_P$60") (pintype "bidirectional"))
    )
    (net (code "130") (name "unconnected-(U$1-PadP$61)") (class "Default")
      (node (ref "U$1") (pin "P$61") (pinfunction "P$61_P$61") (pintype "bidirectional"))
    )
    (net (code "131") (name "unconnected-(U$1-PadP$62)") (class "Default")
      (node (ref "U$1") (pin "P$62") (pinfunction "P$62_P$62") (pintype "bidirectional"))
    )
    (net (code "132") (name "unconnected-(U$1-PadP$63)") (class "Default")
      (node (ref "U$1") (pin "P$63") (pinfunction "P$63_P$63") (pintype "bidirectional"))
    )
    (net (code "133") (name "unconnected-(U$1-PadP$64)") (class "Default")
      (node (ref "U$1") (pin "P$64") (pinfunction "P$64_P$64") (pintype "bidirectional"))
    )
    (net (code "134") (name "unconnected-(U$2-DIO0-Pad20)") (class "Default")
      (node (ref "U$2") (pin "20") (pinfunction "DIO0_20") (pintype "bidirectional"))
    )
    (net (code "135") (name "unconnected-(U$2-DIO1-Pad19)") (class "Default")
      (node (ref "U$2") (pin "19") (pinfunction "DIO1_19") (pintype "bidirectional"))
    )
    (net (code "136") (name "unconnected-(U$2-DIO2-Pad18)") (class "Default")
      (node (ref "U$2") (pin "18") (pinfunction "DIO2_18") (pintype "bidirectional"))
    )
    (net (code "137") (name "unconnected-(U$2-DIO3-Pad17)") (class "Default")
      (node (ref "U$2") (pin "17") (pinfunction "DIO3_17") (pintype "bidirectional"))
    )
    (net (code "138") (name "unconnected-(U$2-DIO4-Pad11)") (class "Default")
      (node (ref "U$2") (pin "11") (pinfunction "DIO4_11") (pintype "bidirectional"))
    )
    (net (code "139") (name "unconnected-(U$2-DIO5-Pad15)") (class "Default")
      (node (ref "U$2") (pin "15") (pinfunction "DIO5_15") (pintype "bidirectional"))
    )
    (net (code "140") (name "unconnected-(U$2-DIO9-Pad13)") (class "Default")
      (node (ref "U$2") (pin "13") (pinfunction "DIO9_13") (pintype "bidirectional"))
    )
    (net (code "141") (name "unconnected-(U$2-DIO11-Pad7)") (class "Default")
      (node (ref "U$2") (pin "7") (pinfunction "DIO11_7") (pintype "bidirectional"))
    )
    (net (code "142") (name "unconnected-(U$2-DIO12-Pad4)") (class "Default")
      (node (ref "U$2") (pin "4") (pinfunction "DIO12_4") (pintype "bidirectional"))
    )
    (net (code "143") (name "unconnected-(U$2-RES-Pad8)") (class "Default")
      (node (ref "U$2") (pin "8") (pinfunction "RES_8") (pintype "bidirectional"))
    )
    (net (code "144") (name "unconnected-(U$2-RES-Pad14)") (class "Default")
      (node (ref "U$2") (pin "14") (pinfunction "RES_14") (pintype "bidirectional"))
    )
    (net (code "145") (name "unconnected-(U$2-RESET-Pad5)") (class "Default")
      (node (ref "U$2") (pin "5") (pinfunction "RESET_5") (pintype "input"))
    )
    (net (code "146") (name "unconnected-(U$2-RSSI-Pad6)") (class "Default")
      (node (ref "U$2") (pin "6") (pinfunction "RSSI_6") (pintype "bidirectional"))
    )
    (net (code "147") (name "unconnected-(U$6-NC-PadP$6)") (class "Default")
      (node (ref "U$6") (pin "P$6") (pinfunction "NC_P$6") (pintype "bidirectional"))
    )
    (net (code "148") (name "unconnected-(U$7-A2-Pad97)") (class "Default")
      (node (ref "U$7") (pin "97") (pinfunction "A2_97") (pintype "bidirectional"))
    )
    (net (code "149") (name "unconnected-(U$7-A3-Pad96)") (class "Default")
      (node (ref "U$7") (pin "96") (pinfunction "A3_96") (pintype "bidirectional"))
    )
    (net (code "150") (name "unconnected-(U$7-A4-Pad95)") (class "Default")
      (node (ref "U$7") (pin "95") (pinfunction "A4_95") (pintype "bidirectional"))
    )
    (net (code "151") (name "unconnected-(U$7-A5-Pad94)") (class "Default")
      (node (ref "U$7") (pin "94") (pinfunction "A5_94") (pintype "bidirectional"))
    )
    (net (code "152") (name "unconnected-(U$7-A6-Pad93)") (class "Default")
      (node (ref "U$7") (pin "93") (pinfunction "A6_93") (pintype "bidirectional"))
    )
    (net (code "153") (name "unconnected-(U$7-A7-Pad92)") (class "Default")
      (node (ref "U$7") (pin "92") (pinfunction "A7_92") (pintype "bidirectional"))
    )
    (net (code "154") (name "unconnected-(U$7-A8-Pad89)") (class "Default")
      (node (ref "U$7") (pin "89") (pinfunction "A8_89") (pintype "bidirectional"))
    )
    (net (code "155") (name "unconnected-(U$7-A9-Pad88)") (class "Default")
      (node (ref "U$7") (pin "88") (pinfunction "A9_88") (pintype "bidirectional"))
    )
    (net (code "156") (name "unconnected-(U$7-A10-Pad87)") (class "Default")
      (node (ref "U$7") (pin "87") (pinfunction "A10_87") (pintype "bidirectional"))
    )
    (net (code "157") (name "unconnected-(U$7-A11-Pad86)") (class "Default")
      (node (ref "U$7") (pin "86") (pinfunction "A11_86") (pintype "bidirectional"))
    )
    (net (code "158") (name "unconnected-(U$7-A12-Pad85)") (class "Default")
      (node (ref "U$7") (pin "85") (pinfunction "A12_85") (pintype "bidirectional"))
    )
    (net (code "159") (name "unconnected-(U$7-A13-Pad84)") (class "Default")
      (node (ref "U$7") (pin "84") (pinfunction "A13_84") (pintype "bidirectional"))
    )
    (net (code "160") (name "unconnected-(U$7-A14-Pad83)") (class "Default")
      (node (ref "U$7") (pin "83") (pinfunction "A14_83") (pintype "bidirectional"))
    )
    (net (code "161") (name "unconnected-(U$7-A15-Pad82)") (class "Default")
      (node (ref "U$7") (pin "82") (pinfunction "A15_82") (pintype "bidirectional"))
    )
    (net (code "162") (name "unconnected-(U$7-A18-Pad79)") (class "Default")
      (node (ref "U$7") (pin "79") (pinfunction "A18_79") (pintype "bidirectional"))
    )
    (net (code "163") (name "unconnected-(U$7-A19-Pad76)") (class "Default")
      (node (ref "U$7") (pin "76") (pinfunction "A19_76") (pintype "bidirectional"))
    )
    (net (code "164") (name "unconnected-(U$7-A20-Pad75)") (class "Default")
      (node (ref "U$7") (pin "75") (pinfunction "A20_75") (pintype "bidirectional"))
    )
    (net (code "165") (name "unconnected-(U$7-A21-Pad74)") (class "Default")
      (node (ref "U$7") (pin "74") (pinfunction "A21_74") (pintype "bidirectional"))
    )
    (net (code "166") (name "unconnected-(U$7-A22-Pad73)") (class "Default")
      (node (ref "U$7") (pin "73") (pinfunction "A22_73") (pintype "bidirectional"))
    )
    (net (code "167") (name "unconnected-(U$7-ADVREF-Pad157)") (class "Default")
      (node (ref "U$7") (pin "157") (pinfunction "ADVREF_157") (pintype "bidirectional"))
    )
    (net (code "168") (name "unconnected-(U$7-BA0{slash}A16-Pad81)") (class "Default")
      (node (ref "U$7") (pin "81") (pinfunction "BA0/A16_81") (pintype "bidirectional"))
    )
    (net (code "169") (name "unconnected-(U$7-BA1{slash}A17-Pad80)") (class "Default")
      (node (ref "U$7") (pin "80") (pinfunction "BA1/A17_80") (pintype "bidirectional"))
    )
    (net (code "170") (name "unconnected-(U$7-CAS-Pad104)") (class "Default")
      (node (ref "U$7") (pin "104") (pinfunction "CAS_104") (pintype "bidirectional"))
    )
    (net (code "171") (name "unconnected-(U$7-CFIOR{slash}NBS1{slash}NWR1-Pad102)") (class "Default")
      (node (ref "U$7") (pin "102") (pinfunction "CFIOR/NBS1/NWR1_102") (pintype "bidirectional"))
    )
    (net (code "172") (name "unconnected-(U$7-CFIOW{slash}NBS3{slash}NWR3-Pad101)") (class "Default")
      (node (ref "U$7") (pin "101") (pinfunction "CFIOW/NBS3/NWR3_101") (pintype "bidirectional"))
    )
    (net (code "173") (name "unconnected-(U$7-CFOE{slash}NRD-Pad69)") (class "Default")
      (node (ref "U$7") (pin "69") (pinfunction "CFOE/NRD_69") (pintype "bidirectional"))
    )
    (net (code "174") (name "unconnected-(U$7-CFWE{slash}NWE{slash}NWR0-Pad70)") (class "Default")
      (node (ref "U$7") (pin "70") (pinfunction "CFWE/NWE/NWR0_70") (pintype "bidirectional"))
    )
    (net (code "175") (name "unconnected-(U$7-D0-Pad106)") (class "Default")
      (node (ref "U$7") (pin "106") (pinfunction "D0_106") (pintype "bidirectional"))
    )
    (net (code "176") (name "unconnected-(U$7-D1-Pad107)") (class "Default")
      (node (ref "U$7") (pin "107") (pinfunction "D1_107") (pintype "bidirectional"))
    )
    (net (code "177") (name "unconnected-(U$7-D2-Pad108)") (class "Default")
      (node (ref "U$7") (pin "108") (pinfunction "D2_108") (pintype "bidirectional"))
    )
    (net (code "178") (name "unconnected-(U$7-D3-Pad109)") (class "Default")
      (node (ref "U$7") (pin "109") (pinfunction "D3_109") (pintype "bidirectional"))
    )
    (net (code "179") (name "unconnected-(U$7-D4-Pad110)") (class "Default")
      (node (ref "U$7") (pin "110") (pinfunction "D4_110") (pintype "bidirectional"))
    )
    (net (code "180") (name "unconnected-(U$7-D5-Pad111)") (class "Default")
      (node (ref "U$7") (pin "111") (pinfunction "D5_111") (pintype "bidirectional"))
    )
    (net (code "181") (name "unconnected-(U$7-D6-Pad112)") (class "Default")
      (node (ref "U$7") (pin "112") (pinfunction "D6_112") (pintype "bidirectional"))
    )
    (net (code "182") (name "unconnected-(U$7-D7-Pad118)") (class "Default")
      (node (ref "U$7") (pin "118") (pinfunction "D7_118") (pintype "bidirectional"))
    )
    (net (code "183") (name "unconnected-(U$7-D8-Pad119)") (class "Default")
      (node (ref "U$7") (pin "119") (pinfunction "D8_119") (pintype "bidirectional"))
    )
    (net (code "184") (name "unconnected-(U$7-D9-Pad120)") (class "Default")
      (node (ref "U$7") (pin "120") (pinfunction "D9_120") (pintype "bidirectional"))
    )
    (net (code "185") (name "unconnected-(U$7-D10-Pad121)") (class "Default")
      (node (ref "U$7") (pin "121") (pinfunction "D10_121") (pintype "bidirectional"))
    )
    (net (code "186") (name "unconnected-(U$7-D11-Pad122)") (class "Default")
      (node (ref "U$7") (pin "122") (pinfunction "D11_122") (pintype "bidirectional"))
    )
    (net (code "187") (name "unconnected-(U$7-D12-Pad123)") (class "Default")
      (node (ref "U$7") (pin "123") (pinfunction "D12_123") (pintype "bidirectional"))
    )
    (net (code "188") (name "unconnected-(U$7-D13-Pad124)") (class "Default")
      (node (ref "U$7") (pin "124") (pinfunction "D13_124") (pintype "bidirectional"))
    )
    (net (code "189") (name "unconnected-(U$7-D14-Pad125)") (class "Default")
      (node (ref "U$7") (pin "125") (pinfunction "D14_125") (pintype "bidirectional"))
    )
    (net (code "190") (name "unconnected-(U$7-D15-Pad126)") (class "Default")
      (node (ref "U$7") (pin "126") (pinfunction "D15_126") (pintype "bidirectional"))
    )
    (net (code "191") (name "unconnected-(U$7-NANDOE-Pad71)") (class "Default")
      (node (ref "U$7") (pin "71") (pinfunction "NANDOE_71") (pintype "bidirectional"))
    )
    (net (code "192") (name "unconnected-(U$7-NANDWE-Pad72)") (class "Default")
      (node (ref "U$7") (pin "72") (pinfunction "NANDWE_72") (pintype "bidirectional"))
    )
    (net (code "193") (name "unconnected-(U$7-NBS0{slash}A0-Pad99)") (class "Default")
      (node (ref "U$7") (pin "99") (pinfunction "NBS0/A0_99") (pintype "bidirectional"))
    )
    (net (code "194") (name "unconnected-(U$7-NC-Pad152)") (class "Default")
      (node (ref "U$7") (pin "152") (pinfunction "NC_152") (pintype "bidirectional"))
    )
    (net (code "195") (name "unconnected-(U$7-NCS0-Pad68)") (class "Default")
      (node (ref "U$7") (pin "68") (pinfunction "NCS0_68") (pintype "bidirectional"))
    )
    (net (code "196") (name "unconnected-(U$7-NWR2{slash}NBS2{slash}A1-Pad98)") (class "Default")
      (node (ref "U$7") (pin "98") (pinfunction "NWR2/NBS2/A1_98") (pintype "bidirectional"))
    )
    (net (code "197") (name "unconnected-(U$7-PA3-Pad182)") (class "Default")
      (node (ref "U$7") (pin "182") (pinfunction "PA3_182") (pintype "bidirectional"))
    )
    (net (code "198") (name "unconnected-(U$7-PA4-Pad183)") (class "Default")
      (node (ref "U$7") (pin "183") (pinfunction "PA4_183") (pintype "bidirectional"))
    )
    (net (code "199") (name "unconnected-(U$7-PA5-Pad184)") (class "Default")
      (node (ref "U$7") (pin "184") (pinfunction "PA5_184") (pintype "bidirectional"))
    )
    (net (code "200") (name "unconnected-(U$7-PA6-Pad185)") (class "Default")
      (node (ref "U$7") (pin "185") (pinfunction "PA6_185") (pintype "bidirectional"))
    )
    (net (code "201") (name "unconnected-(U$7-PA7-Pad186)") (class "Default")
      (node (ref "U$7") (pin "186") (pinfunction "PA7_186") (pintype "bidirectional"))
    )
    (net (code "202") (name "unconnected-(U$7-PA8-Pad189)") (class "Default")
      (node (ref "U$7") (pin "189") (pinfunction "PA8_189") (pintype "bidirectional"))
    )
    (net (code "203") (name "unconnected-(U$7-PA9-Pad190)") (class "Default")
      (node (ref "U$7") (pin "190") (pinfunction "PA9_190") (pintype "bidirectional"))
    )
    (net (code "204") (name "unconnected-(U$7-PA10-Pad191)") (class "Default")
      (node (ref "U$7") (pin "191") (pinfunction "PA10_191") (pintype "bidirectional"))
    )
    (net (code "205") (name "unconnected-(U$7-PA11-Pad192)") (class "Default")
      (node (ref "U$7") (pin "192") (pinfunction "PA11_192") (pintype "bidirectional"))
    )
    (net (code "206") (name "unconnected-(U$7-PA12-Pad193)") (class "Default")
      (node (ref "U$7") (pin "193") (pinfunction "PA12_193") (pintype "bidirectional"))
    )
    (net (code "207") (name "unconnected-(U$7-PA13-Pad194)") (class "Default")
      (node (ref "U$7") (pin "194") (pinfunction "PA13_194") (pintype "bidirectional"))
    )
    (net (code "208") (name "unconnected-(U$7-PA14-Pad195)") (class "Default")
      (node (ref "U$7") (pin "195") (pinfunction "PA14_195") (pintype "bidirectional"))
    )
    (net (code "209") (name "unconnected-(U$7-PA15-Pad196)") (class "Default")
      (node (ref "U$7") (pin "196") (pinfunction "PA15_196") (pintype "bidirectional"))
    )
    (net (code "210") (name "unconnected-(U$7-PA16-Pad197)") (class "Default")
      (node (ref "U$7") (pin "197") (pinfunction "PA16_197") (pintype "bidirectional"))
    )
    (net (code "211") (name "unconnected-(U$7-PA17-Pad198)") (class "Default")
      (node (ref "U$7") (pin "198") (pinfunction "PA17_198") (pintype "bidirectional"))
    )
    (net (code "212") (name "unconnected-(U$7-PA18-Pad201)") (class "Default")
      (node (ref "U$7") (pin "201") (pinfunction "PA18_201") (pintype "bidirectional"))
    )
    (net (code "213") (name "unconnected-(U$7-PA19-Pad202)") (class "Default")
      (node (ref "U$7") (pin "202") (pinfunction "PA19_202") (pintype "bidirectional"))
    )
    (net (code "214") (name "unconnected-(U$7-PA20-Pad205)") (class "Default")
      (node (ref "U$7") (pin "205") (pinfunction "PA20_205") (pintype "bidirectional"))
    )
    (net (code "215") (name "unconnected-(U$7-PA21-Pad206)") (class "Default")
      (node (ref "U$7") (pin "206") (pinfunction "PA21_206") (pintype "bidirectional"))
    )
    (net (code "216") (name "unconnected-(U$7-PA22-Pad207)") (class "Default")
      (node (ref "U$7") (pin "207") (pinfunction "PA22_207") (pintype "bidirectional"))
    )
    (net (code "217") (name "unconnected-(U$7-PA26-Pad3)") (class "Default")
      (node (ref "U$7") (pin "3") (pinfunction "PA26_3") (pintype "bidirectional"))
    )
    (net (code "218") (name "unconnected-(U$7-PA27-Pad4)") (class "Default")
      (node (ref "U$7") (pin "4") (pinfunction "PA27_4") (pintype "bidirectional"))
    )
    (net (code "219") (name "unconnected-(U$7-PA28-Pad7)") (class "Default")
      (node (ref "U$7") (pin "7") (pinfunction "PA28_7") (pintype "bidirectional"))
    )
    (net (code "220") (name "unconnected-(U$7-PA29-Pad8)") (class "Default")
      (node (ref "U$7") (pin "8") (pinfunction "PA29_8") (pintype "bidirectional"))
    )
    (net (code "221") (name "unconnected-(U$7-PB0-Pad9)") (class "Default")
      (node (ref "U$7") (pin "9") (pinfunction "PB0_9") (pintype "bidirectional"))
    )
    (net (code "222") (name "unconnected-(U$7-PB1-Pad10)") (class "Default")
      (node (ref "U$7") (pin "10") (pinfunction "PB1_10") (pintype "bidirectional"))
    )
    (net (code "223") (name "unconnected-(U$7-PB2-Pad11)") (class "Default")
      (node (ref "U$7") (pin "11") (pinfunction "PB2_11") (pintype "bidirectional"))
    )
    (net (code "224") (name "unconnected-(U$7-PB3-Pad12)") (class "Default")
      (node (ref "U$7") (pin "12") (pinfunction "PB3_12") (pintype "bidirectional"))
    )
    (net (code "225") (name "unconnected-(U$7-PB4-Pad15)") (class "Default")
      (node (ref "U$7") (pin "15") (pinfunction "PB4_15") (pintype "bidirectional"))
    )
    (net (code "226") (name "unconnected-(U$7-PB5-Pad16)") (class "Default")
      (node (ref "U$7") (pin "16") (pinfunction "PB5_16") (pintype "bidirectional"))
    )
    (net (code "227") (name "unconnected-(U$7-PB6-Pad17)") (class "Default")
      (node (ref "U$7") (pin "17") (pinfunction "PB6_17") (pintype "bidirectional"))
    )
    (net (code "228") (name "unconnected-(U$7-PB7-Pad18)") (class "Default")
      (node (ref "U$7") (pin "18") (pinfunction "PB7_18") (pintype "bidirectional"))
    )
    (net (code "229") (name "unconnected-(U$7-PB8-Pad19)") (class "Default")
      (node (ref "U$7") (pin "19") (pinfunction "PB8_19") (pintype "bidirectional"))
    )
    (net (code "230") (name "unconnected-(U$7-PB9-Pad20)") (class "Default")
      (node (ref "U$7") (pin "20") (pinfunction "PB9_20") (pintype "bidirectional"))
    )
    (net (code "231") (name "unconnected-(U$7-PB10-Pad161)") (class "Default")
      (node (ref "U$7") (pin "161") (pinfunction "PB10_161") (pintype "bidirectional"))
    )
    (net (code "232") (name "unconnected-(U$7-PB11-Pad162)") (class "Default")
      (node (ref "U$7") (pin "162") (pinfunction "PB11_162") (pintype "bidirectional"))
    )
    (net (code "233") (name "unconnected-(U$7-PB14-Pad21)") (class "Default")
      (node (ref "U$7") (pin "21") (pinfunction "PB14_21") (pintype "bidirectional"))
    )
    (net (code "234") (name "unconnected-(U$7-PB15-Pad22)") (class "Default")
      (node (ref "U$7") (pin "22") (pinfunction "PB15_22") (pintype "bidirectional"))
    )
    (net (code "235") (name "unconnected-(U$7-PB16-Pad23)") (class "Default")
      (node (ref "U$7") (pin "23") (pinfunction "PB16_23") (pintype "bidirectional"))
    )
    (net (code "236") (name "unconnected-(U$7-PB17-Pad26)") (class "Default")
      (node (ref "U$7") (pin "26") (pinfunction "PB17_26") (pintype "bidirectional"))
    )
    (net (code "237") (name "unconnected-(U$7-PB18-Pad27)") (class "Default")
      (node (ref "U$7") (pin "27") (pinfunction "PB18_27") (pintype "bidirectional"))
    )
    (net (code "238") (name "unconnected-(U$7-PB19-Pad28)") (class "Default")
      (node (ref "U$7") (pin "28") (pinfunction "PB19_28") (pintype "bidirectional"))
    )
    (net (code "239") (name "unconnected-(U$7-PC0-Pad158)") (class "Default")
      (node (ref "U$7") (pin "158") (pinfunction "PC0_158") (pintype "bidirectional"))
    )
    (net (code "240") (name "unconnected-(U$7-PC1-Pad159)") (class "Default")
      (node (ref "U$7") (pin "159") (pinfunction "PC1_159") (pintype "bidirectional"))
    )
    (net (code "241") (name "unconnected-(U$7-PC4-Pad62)") (class "Default")
      (node (ref "U$7") (pin "62") (pinfunction "PC4_62") (pintype "bidirectional"))
    )
    (net (code "242") (name "unconnected-(U$7-PC5-Pad67)") (class "Default")
      (node (ref "U$7") (pin "67") (pinfunction "PC5_67") (pintype "bidirectional"))
    )
    (net (code "243") (name "unconnected-(U$7-PC6-Pad63)") (class "Default")
      (node (ref "U$7") (pin "63") (pinfunction "PC6_63") (pintype "bidirectional"))
    )
    (net (code "244") (name "unconnected-(U$7-PC7-Pad64)") (class "Default")
      (node (ref "U$7") (pin "64") (pinfunction "PC7_64") (pintype "bidirectional"))
    )
    (net (code "245") (name "unconnected-(U$7-PC8-Pad61)") (class "Default")
      (node (ref "U$7") (pin "61") (pinfunction "PC8_61") (pintype "bidirectional"))
    )
    (net (code "246") (name "unconnected-(U$7-PC9-Pad60)") (class "Default")
      (node (ref "U$7") (pin "60") (pinfunction "PC9_60") (pintype "bidirectional"))
    )
    (net (code "247") (name "unconnected-(U$7-PC10-Pad58)") (class "Default")
      (node (ref "U$7") (pin "58") (pinfunction "PC10_58") (pintype "bidirectional"))
    )
    (net (code "248") (name "unconnected-(U$7-PC11-Pad57)") (class "Default")
      (node (ref "U$7") (pin "57") (pinfunction "PC11_57") (pintype "bidirectional"))
    )
    (net (code "249") (name "unconnected-(U$7-PC13-Pad56)") (class "Default")
      (node (ref "U$7") (pin "56") (pinfunction "PC13_56") (pintype "bidirectional"))
    )
    (net (code "250") (name "unconnected-(U$7-PC14-Pad59)") (class "Default")
      (node (ref "U$7") (pin "59") (pinfunction "PC14_59") (pintype "bidirectional"))
    )
    (net (code "251") (name "unconnected-(U$7-PC15-Pad127)") (class "Default")
      (node (ref "U$7") (pin "127") (pinfunction "PC15_127") (pintype "bidirectional"))
    )
    (net (code "252") (name "unconnected-(U$7-PC16-Pad128)") (class "Default")
      (node (ref "U$7") (pin "128") (pinfunction "PC16_128") (pintype "bidirectional"))
    )
    (net (code "253") (name "unconnected-(U$7-PC17-Pad129)") (class "Default")
      (node (ref "U$7") (pin "129") (pinfunction "PC17_129") (pintype "bidirectional"))
    )
    (net (code "254") (name "unconnected-(U$7-PC18-Pad130)") (class "Default")
      (node (ref "U$7") (pin "130") (pinfunction "PC18_130") (pintype "bidirectional"))
    )
    (net (code "255") (name "unconnected-(U$7-PC19-Pad131)") (class "Default")
      (node (ref "U$7") (pin "131") (pinfunction "PC19_131") (pintype "bidirectional"))
    )
    (net (code "256") (name "unconnected-(U$7-PC20-Pad134)") (class "Default")
      (node (ref "U$7") (pin "134") (pinfunction "PC20_134") (pintype "bidirectional"))
    )
    (net (code "257") (name "unconnected-(U$7-PC21-Pad135)") (class "Default")
      (node (ref "U$7") (pin "135") (pinfunction "PC21_135") (pintype "bidirectional"))
    )
    (net (code "258") (name "unconnected-(U$7-PC22-Pad136)") (class "Default")
      (node (ref "U$7") (pin "136") (pinfunction "PC22_136") (pintype "bidirectional"))
    )
    (net (code "259") (name "unconnected-(U$7-PC23-Pad137)") (class "Default")
      (node (ref "U$7") (pin "137") (pinfunction "PC23_137") (pintype "bidirectional"))
    )
    (net (code "260") (name "unconnected-(U$7-PC24-Pad138)") (class "Default")
      (node (ref "U$7") (pin "138") (pinfunction "PC24_138") (pintype "bidirectional"))
    )
    (net (code "261") (name "unconnected-(U$7-PC25-Pad139)") (class "Default")
      (node (ref "U$7") (pin "139") (pinfunction "PC25_139") (pintype "bidirectional"))
    )
    (net (code "262") (name "unconnected-(U$7-PC26-Pad140)") (class "Default")
      (node (ref "U$7") (pin "140") (pinfunction "PC26_140") (pintype "bidirectional"))
    )
    (net (code "263") (name "unconnected-(U$7-PC27-Pad141)") (class "Default")
      (node (ref "U$7") (pin "141") (pinfunction "PC27_141") (pintype "bidirectional"))
    )
    (net (code "264") (name "unconnected-(U$7-PC28-Pad142)") (class "Default")
      (node (ref "U$7") (pin "142") (pinfunction "PC28_142") (pintype "bidirectional"))
    )
    (net (code "265") (name "unconnected-(U$7-PC29-Pad143)") (class "Default")
      (node (ref "U$7") (pin "143") (pinfunction "PC29_143") (pintype "bidirectional"))
    )
    (net (code "266") (name "unconnected-(U$7-PC30-Pad144)") (class "Default")
      (node (ref "U$7") (pin "144") (pinfunction "PC30_144") (pintype "bidirectional"))
    )
    (net (code "267") (name "unconnected-(U$7-PC31-Pad145)") (class "Default")
      (node (ref "U$7") (pin "145") (pinfunction "PC31_145") (pintype "bidirectional"))
    )
    (net (code "268") (name "unconnected-(U$7-RAS-Pad105)") (class "Default")
      (node (ref "U$7") (pin "105") (pinfunction "RAS_105") (pintype "bidirectional"))
    )
    (net (code "269") (name "unconnected-(U$7-SDA10-Pad100)") (class "Default")
      (node (ref "U$7") (pin "100") (pinfunction "SDA10_100") (pintype "bidirectional"))
    )
    (net (code "270") (name "unconnected-(U$7-SDCKE-Pad117)") (class "Default")
      (node (ref "U$7") (pin "117") (pinfunction "SDCKE_117") (pintype "bidirectional"))
    )
    (net (code "271") (name "unconnected-(U$7-SDCLK-Pad115)") (class "Default")
      (node (ref "U$7") (pin "115") (pinfunction "SDCLK_115") (pintype "bidirectional"))
    )
    (net (code "272") (name "unconnected-(U$7-SDCS{slash}NCS1-Pad103)") (class "Default")
      (node (ref "U$7") (pin "103") (pinfunction "SDCS/NCS1_103") (pintype "bidirectional"))
    )
    (net (code "273") (name "unconnected-(U$7-SDWE-Pad116)") (class "Default")
      (node (ref "U$7") (pin "116") (pinfunction "SDWE_116") (pintype "bidirectional"))
    )
    (net (code "274") (name "unconnected-(U$7-WKUP-Pad48)") (class "Default")
      (node (ref "U$7") (pin "48") (pinfunction "WKUP_48") (pintype "bidirectional"))
    )
    (net (code "275") (name "unconnected-(U$9-NC-PadP$6)") (class "Default")
      (node (ref "U$9") (pin "P$6") (pinfunction "NC_P$6") (pintype "bidirectional"))
    )
    (net (code "276") (name "unconnected-(X1-Pad1)") (class "Default")
      (node (ref "X1") (pin "1") (pinfunction "1_1") (pintype "passive"))
    )
    (net (code "277") (name "unconnected-(X1-Pad4)") (class "Default")
      (node (ref "X1") (pin "4") (pinfunction "4_4") (pintype "passive"))
    )
    (net (code "278") (name "unconnected-(X1-Pad6)") (class "Default")
      (node (ref "X1") (pin "6") (pinfunction "6_6") (pintype "passive"))
    )
    (net (code "279") (name "unconnected-(X1-Pad9)") (class "Default")
      (node (ref "X1") (pin "9") (pinfunction "9_9") (pintype "passive"))
    )
  )
)
